# ARM_board.net
KiCad netlist of a schematic drawn in EAGLE
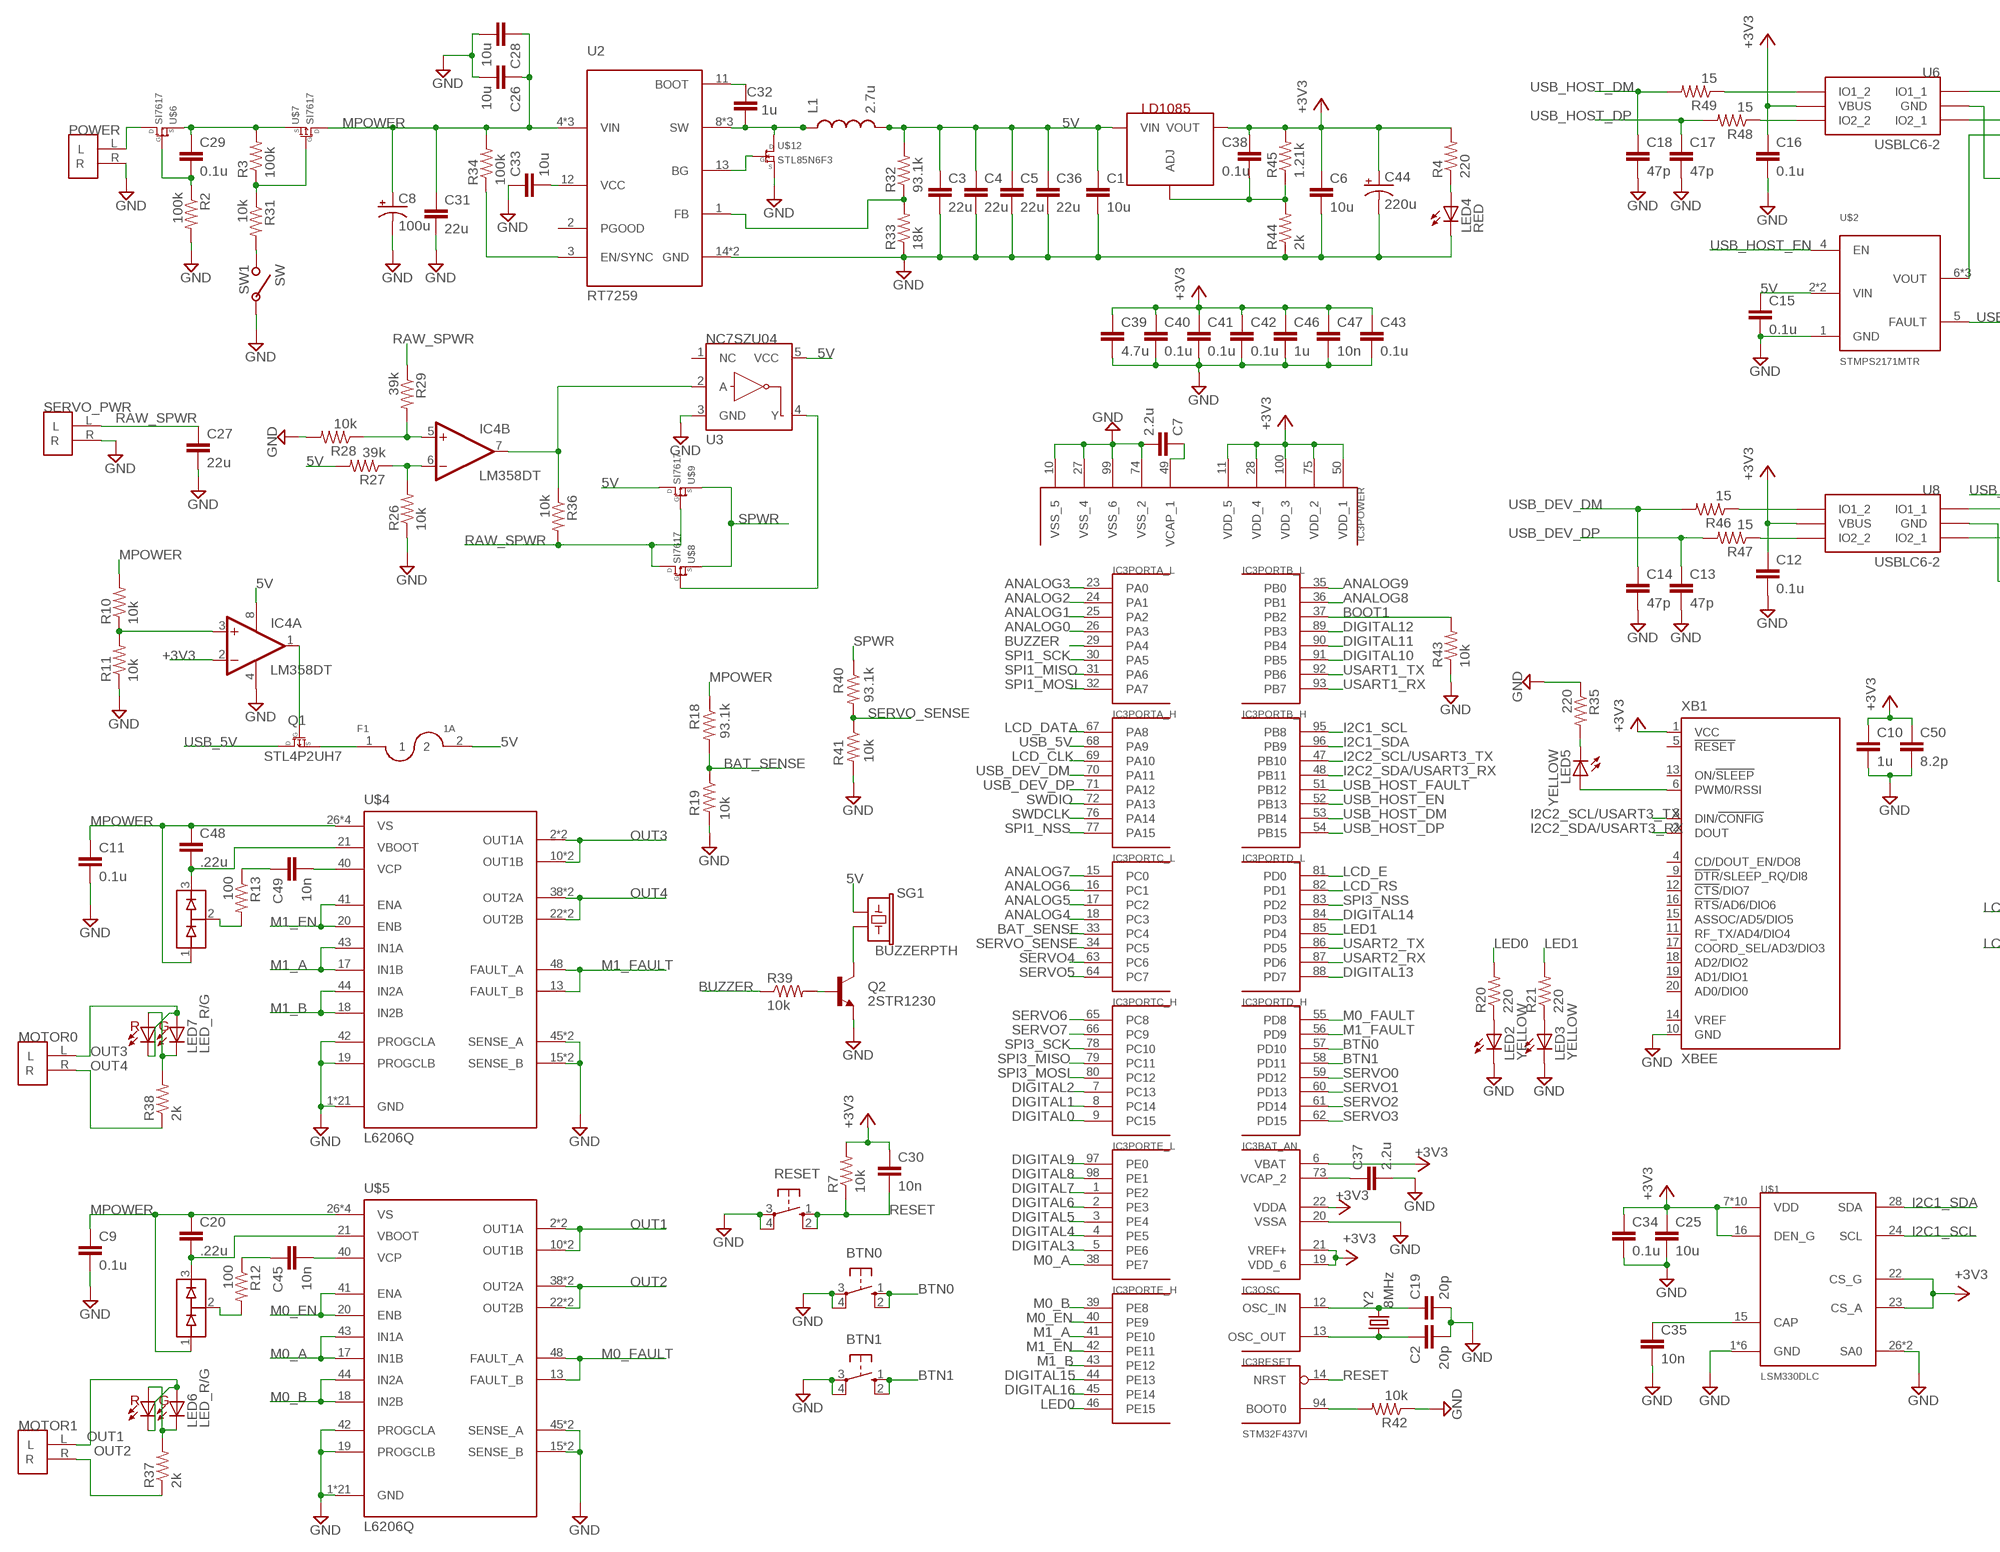
[diagram p0: schematic, sheet 1, part 1 of 2]
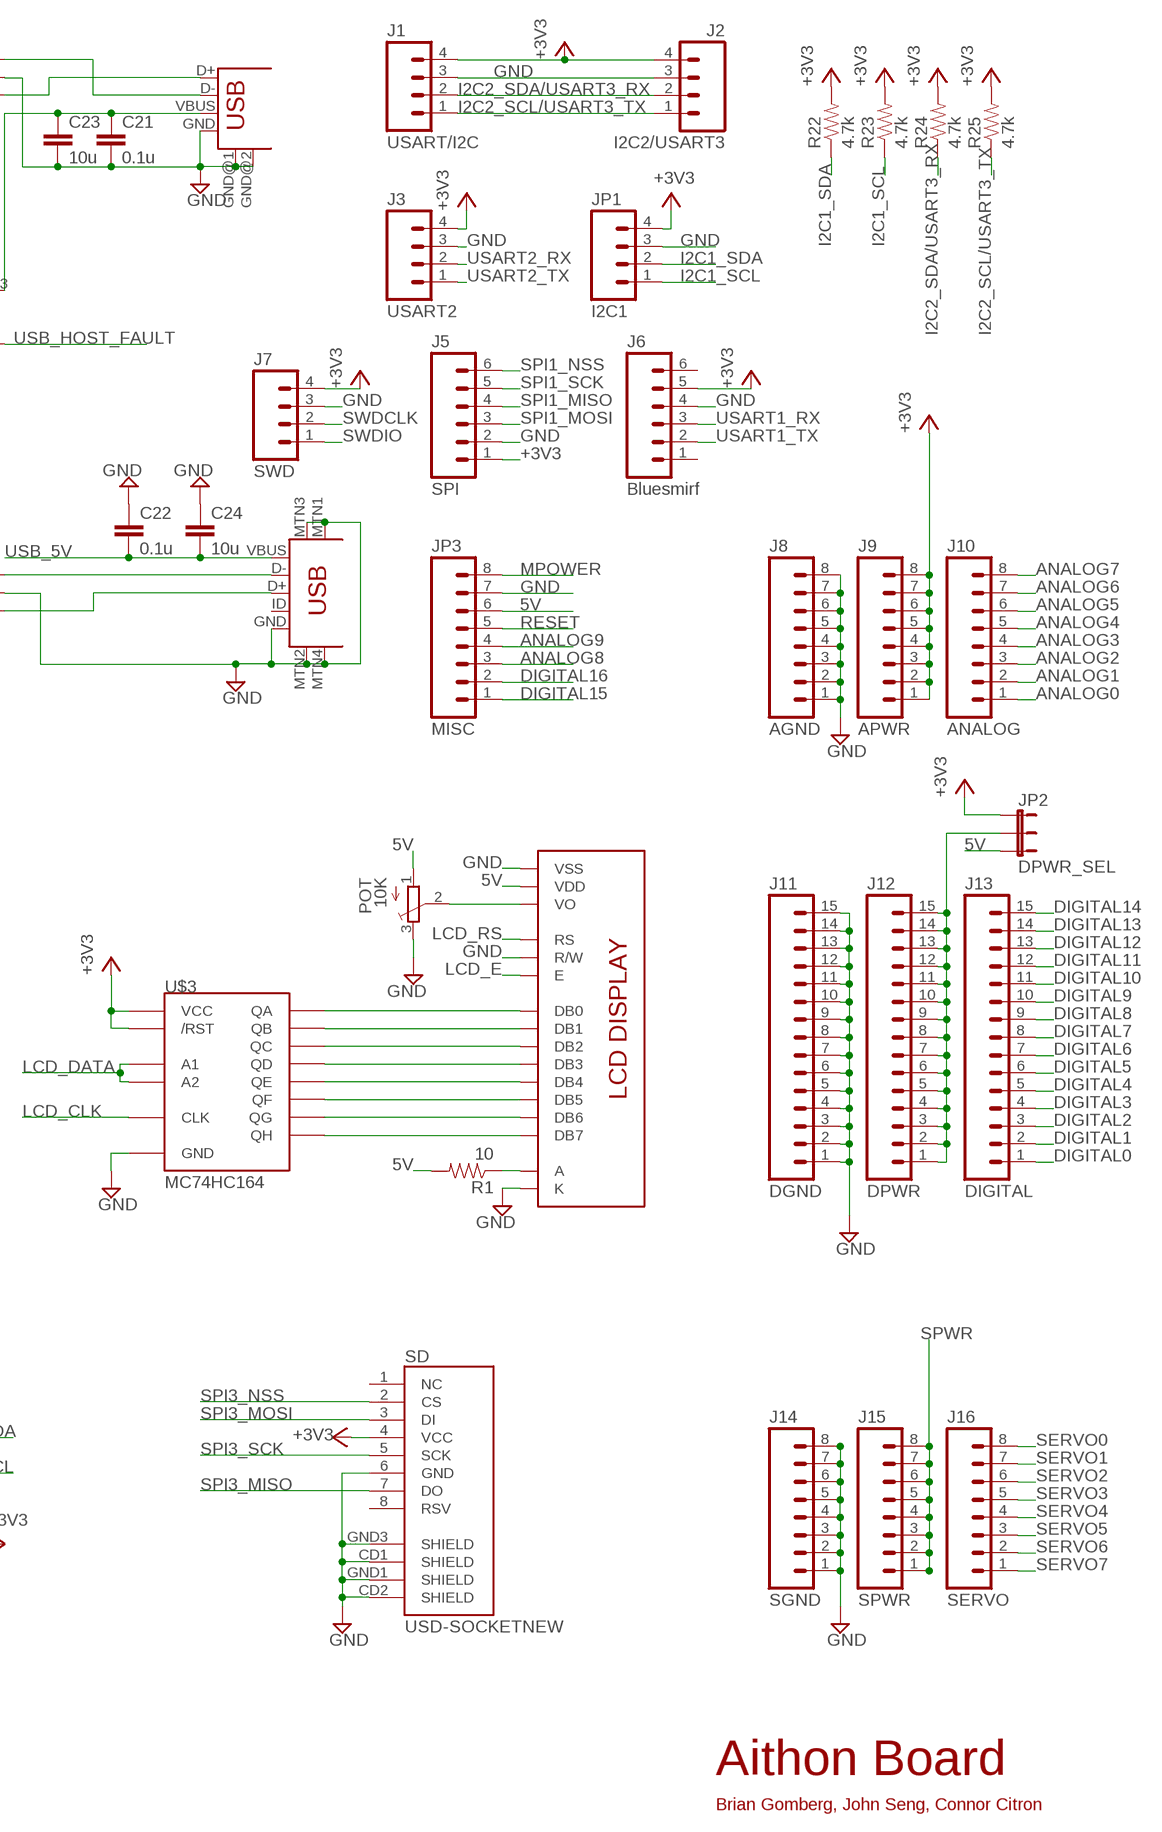
[diagram p1: schematic, sheet 1, part 2 of 2]

(export (version "E")
  (design (tool "Eeschema 10.0.6"))
  (components
    (comp (ref "BTN0")
      (value "10-XX")
      (footprint "eagle-import:B3F-10XX")
      (fields (field (name "MPN") "B3F-1000"))
      (libsource (lib "eagle-import") (part "10-XX"))
    )
    (comp (ref "BTN1")
      (value "10-XX")
      (footprint "eagle-import:B3F-10XX")
      (fields (field (name "MPN") "B3F-1000"))
      (libsource (lib "eagle-import") (part "10-XX"))
    )
    (comp (ref "C1")
      (value "10u")
      (footprint "eagle-import:0603-CAP")
      (libsource (lib "eagle-import") (part "CAP0603-CAP"))
    )
    (comp (ref "C2")
      (value "20p")
      (footprint "eagle-import:0402-CAP")
      (libsource (lib "eagle-import") (part "CAP0402-CAP"))
    )
    (comp (ref "C3")
      (value "22u")
      (footprint "eagle-import:0805")
      (libsource (lib "eagle-import") (part "CAP0805"))
    )
    (comp (ref "C4")
      (value "22u")
      (footprint "eagle-import:0805")
      (libsource (lib "eagle-import") (part "CAP0805"))
    )
    (comp (ref "C5")
      (value "22u")
      (footprint "eagle-import:0805")
      (libsource (lib "eagle-import") (part "CAP0805"))
    )
    (comp (ref "C6")
      (value "10u")
      (footprint "eagle-import:0603-CAP")
      (libsource (lib "eagle-import") (part "CAP0603-CAP"))
    )
    (comp (ref "C7")
      (value "2.2u")
      (footprint "eagle-import:0402-CAP")
      (libsource (lib "eagle-import") (part "CAP0402-CAP"))
    )
    (comp (ref "C8")
      (value "100u")
      (footprint "eagle-import:PANASONIC_D")
      (libsource (lib "eagle-import") (part "CAP_POLD"))
    )
    (comp (ref "C9")
      (value "0.1u")
      (footprint "eagle-import:0603-CAP")
      (libsource (lib "eagle-import") (part "CAP0603-CAP"))
    )
    (comp (ref "C10")
      (value "1u")
      (footprint "eagle-import:0603-CAP")
      (libsource (lib "eagle-import") (part "CAP0603-CAP"))
    )
    (comp (ref "C11")
      (value "0.1u")
      (footprint "eagle-import:0805")
      (libsource (lib "eagle-import") (part "CAP0805"))
    )
    (comp (ref "C12")
      (value "0.1u")
      (footprint "eagle-import:0402-CAP")
      (libsource (lib "eagle-import") (part "CAP0402-CAP"))
    )
    (comp (ref "C13")
      (value "47p")
      (footprint "eagle-import:0402-CAP")
      (libsource (lib "eagle-import") (part "CAP0402-CAP"))
    )
    (comp (ref "C14")
      (value "47p")
      (footprint "eagle-import:0402-CAP")
      (libsource (lib "eagle-import") (part "CAP0402-CAP"))
    )
    (comp (ref "C15")
      (value "0.1u")
      (footprint "eagle-import:0402-CAP")
      (libsource (lib "eagle-import") (part "CAP0402-CAP"))
    )
    (comp (ref "C16")
      (value "0.1u")
      (footprint "eagle-import:0402-CAP")
      (libsource (lib "eagle-import") (part "CAP0402-CAP"))
    )
    (comp (ref "C17")
      (value "47p")
      (footprint "eagle-import:0402-CAP")
      (libsource (lib "eagle-import") (part "CAP0402-CAP"))
    )
    (comp (ref "C18")
      (value "47p")
      (footprint "eagle-import:0402-CAP")
      (libsource (lib "eagle-import") (part "CAP0402-CAP"))
    )
    (comp (ref "C19")
      (value "20p")
      (footprint "eagle-import:0402-CAP")
      (libsource (lib "eagle-import") (part "CAP0402-CAP"))
    )
    (comp (ref "C20")
      (value ".22u")
      (footprint "eagle-import:0402-CAP")
      (libsource (lib "eagle-import") (part "CAP0402-CAP"))
    )
    (comp (ref "C21")
      (value "0.1u")
      (footprint "eagle-import:0402-CAP")
      (libsource (lib "eagle-import") (part "CAP0402-CAP"))
    )
    (comp (ref "C22")
      (value "0.1u")
      (footprint "eagle-import:0402-CAP")
      (libsource (lib "eagle-import") (part "CAP0402-CAP"))
    )
    (comp (ref "C23")
      (value "10u")
      (footprint "eagle-import:0805")
      (libsource (lib "eagle-import") (part "CAP0805"))
    )
    (comp (ref "C24")
      (value "10u")
      (footprint "eagle-import:0805")
      (libsource (lib "eagle-import") (part "CAP0805"))
    )
    (comp (ref "C25")
      (value "10u")
      (footprint "eagle-import:0603-CAP")
      (libsource (lib "eagle-import") (part "CAP0603-CAP"))
    )
    (comp (ref "C26")
      (value "10u")
      (footprint "eagle-import:0805")
      (libsource (lib "eagle-import") (part "CAP0805"))
    )
    (comp (ref "C27")
      (value "22u")
      (footprint "eagle-import:1206")
      (libsource (lib "eagle-import") (part "CAP1206"))
    )
    (comp (ref "C28")
      (value "10u")
      (footprint "eagle-import:0805")
      (libsource (lib "eagle-import") (part "CAP0805"))
    )
    (comp (ref "C29")
      (value "0.1u")
      (footprint "eagle-import:0402-CAP")
      (libsource (lib "eagle-import") (part "CAP0402-CAP"))
    )
    (comp (ref "C30")
      (value "10n")
      (footprint "eagle-import:0402-CAP")
      (libsource (lib "eagle-import") (part "CAP0402-CAP"))
    )
    (comp (ref "C31")
      (value "22u")
      (footprint "eagle-import:1206")
      (libsource (lib "eagle-import") (part "CAP1206"))
    )
    (comp (ref "C32")
      (value "1u")
      (footprint "eagle-import:0603-CAP")
      (libsource (lib "eagle-import") (part "CAP0603-CAP"))
    )
    (comp (ref "C33")
      (value "10u")
      (footprint "eagle-import:0603-CAP")
      (libsource (lib "eagle-import") (part "CAP0603-CAP"))
    )
    (comp (ref "C34")
      (value "0.1u")
      (footprint "eagle-import:0402-CAP")
      (libsource (lib "eagle-import") (part "CAP0402-CAP"))
    )
    (comp (ref "C35")
      (value "10n")
      (footprint "eagle-import:0402-CAP")
      (libsource (lib "eagle-import") (part "CAP0402-CAP"))
    )
    (comp (ref "C36")
      (value "22u")
      (footprint "eagle-import:0805")
      (libsource (lib "eagle-import") (part "CAP0805"))
    )
    (comp (ref "C37")
      (value "2.2u")
      (footprint "eagle-import:0402-CAP")
      (libsource (lib "eagle-import") (part "CAP0402-CAP"))
    )
    (comp (ref "C38")
      (value "0.1u")
      (footprint "eagle-import:0402-CAP")
      (libsource (lib "eagle-import") (part "CAP0402-CAP"))
    )
    (comp (ref "C39")
      (value "4.7u")
      (footprint "eagle-import:0603-CAP")
      (libsource (lib "eagle-import") (part "CAP0603-CAP"))
    )
    (comp (ref "C40")
      (value "0.1u")
      (footprint "eagle-import:0402-CAP")
      (libsource (lib "eagle-import") (part "CAP0402-CAP"))
    )
    (comp (ref "C41")
      (value "0.1u")
      (footprint "eagle-import:0402-CAP")
      (libsource (lib "eagle-import") (part "CAP0402-CAP"))
    )
    (comp (ref "C42")
      (value "0.1u")
      (footprint "eagle-import:0402-CAP")
      (libsource (lib "eagle-import") (part "CAP0402-CAP"))
    )
    (comp (ref "C43")
      (value "0.1u")
      (footprint "eagle-import:0402-CAP")
      (libsource (lib "eagle-import") (part "CAP0402-CAP"))
    )
    (comp (ref "C44")
      (value "220u")
      (footprint "eagle-import:PANASONIC_D")
      (libsource (lib "eagle-import") (part "CAP_POLD"))
    )
    (comp (ref "C45")
      (value "10n")
      (footprint "eagle-import:0402-CAP")
      (libsource (lib "eagle-import") (part "CAP0402-CAP"))
    )
    (comp (ref "C46")
      (value "1u")
      (footprint "eagle-import:0402-CAP")
      (libsource (lib "eagle-import") (part "CAP0402-CAP"))
    )
    (comp (ref "C47")
      (value "10n")
      (footprint "eagle-import:0402-CAP")
      (libsource (lib "eagle-import") (part "CAP0402-CAP"))
    )
    (comp (ref "C48")
      (value ".22u")
      (footprint "eagle-import:0402-CAP")
      (libsource (lib "eagle-import") (part "CAP0402-CAP"))
    )
    (comp (ref "C49")
      (value "10n")
      (footprint "eagle-import:0402-CAP")
      (libsource (lib "eagle-import") (part "CAP0402-CAP"))
    )
    (comp (ref "C50")
      (value "8.2p")
      (footprint "eagle-import:0402-CAP")
      (libsource (lib "eagle-import") (part "CAP0402-CAP"))
    )
    (comp (ref "F1")
      (value "1A")
      (footprint "eagle-import:1206")
      (libsource (lib "eagle-import") (part "POLYFUSE"))
    )
    (comp (ref "IC3")
      (value "STM32F437VI")
      (footprint "eagle-import:TQFP100")
      (libsource (lib "eagle-import") (part "STM32F407VET"))
    )
    (comp (ref "IC4")
      (value "LM358DT")
      (footprint "eagle-import:SO08")
      (libsource (lib "eagle-import") (part "LM358D"))
    )
    (comp (ref "J1")
      (value "USART/I2C")
      (footprint "eagle-import:1X04")
      (libsource (lib "eagle-import") (part "M04PTH"))
    )
    (comp (ref "J2")
      (value "I2C2/USART3")
      (footprint "eagle-import:1X04")
      (libsource (lib "eagle-import") (part "M04PTH"))
    )
    (comp (ref "J3")
      (value "USART2")
      (footprint "eagle-import:1X04")
      (libsource (lib "eagle-import") (part "M04PTH"))
    )
    (comp (ref "J5")
      (value "SPI")
      (footprint "eagle-import:1X06")
      (libsource (lib "eagle-import") (part "M06SIP"))
    )
    (comp (ref "J6")
      (value "Bluesmirf")
      (footprint "eagle-import:1X06")
      (libsource (lib "eagle-import") (part "M06SIP"))
    )
    (comp (ref "J7")
      (value "SWD")
      (footprint "eagle-import:1X04")
      (libsource (lib "eagle-import") (part "M04PTH"))
    )
    (comp (ref "J8")
      (value "AGND")
      (footprint "eagle-import:1X08")
      (libsource (lib "eagle-import") (part "M081X08"))
    )
    (comp (ref "J9")
      (value "APWR")
      (footprint "eagle-import:1X08")
      (libsource (lib "eagle-import") (part "M081X08"))
    )
    (comp (ref "J10")
      (value "ANALOG")
      (footprint "eagle-import:1X08")
      (libsource (lib "eagle-import") (part "M081X08"))
    )
    (comp (ref "J11")
      (value "DGND")
      (footprint "eagle-import:1X15")
      (libsource (lib "eagle-import") (part "M15"))
    )
    (comp (ref "J12")
      (value "DPWR")
      (footprint "eagle-import:1X15")
      (libsource (lib "eagle-import") (part "M15"))
    )
    (comp (ref "J13")
      (value "DIGITAL")
      (footprint "eagle-import:1X15")
      (libsource (lib "eagle-import") (part "M15"))
    )
    (comp (ref "J14")
      (value "SGND")
      (footprint "eagle-import:1X08")
      (libsource (lib "eagle-import") (part "M081X08"))
    )
    (comp (ref "J15")
      (value "SPWR")
      (footprint "eagle-import:1X08")
      (libsource (lib "eagle-import") (part "M081X08"))
    )
    (comp (ref "J16")
      (value "SERVO")
      (footprint "eagle-import:1X08")
      (libsource (lib "eagle-import") (part "M081X08"))
    )
    (comp (ref "JP1")
      (value "I2C1")
      (footprint "eagle-import:1X04")
      (libsource (lib "eagle-import") (part "M04PTH"))
    )
    (comp (ref "JP2")
      (value "DPWR_SEL")
      (footprint "eagle-import:1X03")
      (libsource (lib "eagle-import") (part "JUMPER-3PTH"))
    )
    (comp (ref "JP3")
      (value "MISC")
      (footprint "eagle-import:1X08")
      (libsource (lib "eagle-import") (part "M081X08"))
    )
    (comp (ref "L1")
      (value "2.7u")
      (footprint "eagle-import:INDUCTOR")
      (libsource (lib "eagle-import") (part "INDUCTOR"))
    )
    (comp (ref "LCD")
      (value "LCD_DISPLAY")
      (footprint "eagle-import:LCD")
      (libsource (lib "eagle-import") (part "LCD_DISPLAY"))
    )
    (comp (ref "LD1085")
      (value "AP1084")
      (footprint "eagle-import:DPAK")
      (libsource (lib "eagle-import") (part "AP1084"))
    )
    (comp (ref "LED2")
      (value "YELLOW")
      (footprint "eagle-import:CHIP-LED0603")
      (libsource (lib "eagle-import") (part "LEDCHIP-LED0603"))
    )
    (comp (ref "LED3")
      (value "YELLOW")
      (footprint "eagle-import:CHIP-LED0603")
      (libsource (lib "eagle-import") (part "LEDCHIP-LED0603"))
    )
    (comp (ref "LED4")
      (value "RED")
      (footprint "eagle-import:CHIP-LED0603")
      (libsource (lib "eagle-import") (part "LEDCHIP-LED0603"))
    )
    (comp (ref "LED5")
      (value "YELLOW")
      (footprint "eagle-import:CHIP-LED0603")
      (libsource (lib "eagle-import") (part "LEDCHIP-LED0603"))
    )
    (comp (ref "LED6")
      (value "LED_R/G")
      (footprint "eagle-import:LED-0606")
      (libsource (lib "eagle-import") (part "LED_BICOLOR"))
    )
    (comp (ref "LED7")
      (value "LED_R/G")
      (footprint "eagle-import:LED-0606")
      (libsource (lib "eagle-import") (part "LED_BICOLOR"))
    )
    (comp (ref "MOTOR0")
      (value "2POS_TERMINAL")
      (footprint "eagle-import:2POS_TERMINAL")
      (libsource (lib "eagle-import") (part "2POS_TERMINAL"))
    )
    (comp (ref "MOTOR1")
      (value "2POS_TERMINAL")
      (footprint "eagle-import:2POS_TERMINAL")
      (libsource (lib "eagle-import") (part "2POS_TERMINAL"))
    )
    (comp (ref "POT")
      (value "10K")
      (footprint "eagle-import:POT")
      (libsource (lib "eagle-import") (part "POT"))
    )
    (comp (ref "POWER")
      (value "2POS_TERMINAL")
      (footprint "eagle-import:2POS_TERMINAL")
      (libsource (lib "eagle-import") (part "2POS_TERMINAL"))
    )
    (comp (ref "Q1")
      (value "STL4P2UH7")
      (footprint "eagle-import:POWERFLAT")
      (libsource (lib "eagle-import") (part "STL4P2UH7"))
    )
    (comp (ref "Q2")
      (value "2STR1230")
      (footprint "eagle-import:SOT23-3")
      (libsource (lib "eagle-import") (part "TRANSISTOR_NPNSOT23-3"))
    )
    (comp (ref "R1")
      (value "10")
      (footprint "eagle-import:0402-RES")
      (libsource (lib "eagle-import") (part "RESISTOR0402-RES"))
    )
    (comp (ref "R2")
      (value "100k")
      (footprint "eagle-import:0402-RES")
      (libsource (lib "eagle-import") (part "RESISTOR0402-RES"))
    )
    (comp (ref "R3")
      (value "100k")
      (footprint "eagle-import:0402-RES")
      (libsource (lib "eagle-import") (part "RESISTOR0402-RES"))
    )
    (comp (ref "R4")
      (value "220")
      (footprint "eagle-import:0402-RES")
      (libsource (lib "eagle-import") (part "RESISTOR0402-RES"))
    )
    (comp (ref "R7")
      (value "10k")
      (footprint "eagle-import:0402-RES")
      (libsource (lib "eagle-import") (part "RESISTOR0402-RES"))
    )
    (comp (ref "R10")
      (value "10k")
      (footprint "eagle-import:0402-RES")
      (libsource (lib "eagle-import") (part "RESISTOR0402-RES"))
    )
    (comp (ref "R11")
      (value "10k")
      (footprint "eagle-import:0402-RES")
      (libsource (lib "eagle-import") (part "RESISTOR0402-RES"))
    )
    (comp (ref "R12")
      (value "100")
      (footprint "eagle-import:0402-RES")
      (libsource (lib "eagle-import") (part "RESISTOR0402-RES"))
    )
    (comp (ref "R13")
      (value "100")
      (footprint "eagle-import:0402-RES")
      (libsource (lib "eagle-import") (part "RESISTOR0402-RES"))
    )
    (comp (ref "R18")
      (value "93.1k")
      (footprint "eagle-import:0402-RES")
      (libsource (lib "eagle-import") (part "RESISTOR0402-RES"))
    )
    (comp (ref "R19")
      (value "10k")
      (footprint "eagle-import:0402-RES")
      (libsource (lib "eagle-import") (part "RESISTOR0402-RES"))
    )
    (comp (ref "R20")
      (value "220")
      (footprint "eagle-import:0402-RES")
      (libsource (lib "eagle-import") (part "RESISTOR0402-RES"))
    )
    (comp (ref "R21")
      (value "220")
      (footprint "eagle-import:0402-RES")
      (libsource (lib "eagle-import") (part "RESISTOR0402-RES"))
    )
    (comp (ref "R22")
      (value "4.7k")
      (footprint "eagle-import:0402-RES")
      (libsource (lib "eagle-import") (part "RESISTOR0402-RES"))
    )
    (comp (ref "R23")
      (value "4.7k")
      (footprint "eagle-import:0402-RES")
      (libsource (lib "eagle-import") (part "RESISTOR0402-RES"))
    )
    (comp (ref "R24")
      (value "4.7k")
      (footprint "eagle-import:0402-RES")
      (libsource (lib "eagle-import") (part "RESISTOR0402-RES"))
    )
    (comp (ref "R25")
      (value "4.7k")
      (footprint "eagle-import:0402-RES")
      (libsource (lib "eagle-import") (part "RESISTOR0402-RES"))
    )
    (comp (ref "R26")
      (value "10k")
      (footprint "eagle-import:0402-RES")
      (libsource (lib "eagle-import") (part "RESISTOR0402-RES"))
    )
    (comp (ref "R27")
      (value "39k")
      (footprint "eagle-import:0402-RES")
      (libsource (lib "eagle-import") (part "RESISTOR0402-RES"))
    )
    (comp (ref "R28")
      (value "10k")
      (footprint "eagle-import:0402-RES")
      (libsource (lib "eagle-import") (part "RESISTOR0402-RES"))
    )
    (comp (ref "R29")
      (value "39k")
      (footprint "eagle-import:0402-RES")
      (libsource (lib "eagle-import") (part "RESISTOR0402-RES"))
    )
    (comp (ref "R31")
      (value "10k")
      (footprint "eagle-import:0402-RES")
      (libsource (lib "eagle-import") (part "RESISTOR0402-RES"))
    )
    (comp (ref "R32")
      (value "93.1k")
      (footprint "eagle-import:0402-RES")
      (libsource (lib "eagle-import") (part "RESISTOR0402-RES"))
    )
    (comp (ref "R33")
      (value "18k")
      (footprint "eagle-import:0402-RES")
      (libsource (lib "eagle-import") (part "RESISTOR0402-RES"))
    )
    (comp (ref "R34")
      (value "100k")
      (footprint "eagle-import:0402-RES")
      (libsource (lib "eagle-import") (part "RESISTOR0402-RES"))
    )
    (comp (ref "R35")
      (value "220")
      (footprint "eagle-import:0402-RES")
      (libsource (lib "eagle-import") (part "RESISTOR0402-RES"))
    )
    (comp (ref "R36")
      (value "10k")
      (footprint "eagle-import:0402-RES")
      (libsource (lib "eagle-import") (part "RESISTOR0402-RES"))
    )
    (comp (ref "R37")
      (value "2k")
      (footprint "eagle-import:0402-RES")
      (libsource (lib "eagle-import") (part "RESISTOR0402-RES"))
    )
    (comp (ref "R38")
      (value "2k")
      (footprint "eagle-import:0402-RES")
      (libsource (lib "eagle-import") (part "RESISTOR0402-RES"))
    )
    (comp (ref "R39")
      (value "10k")
      (footprint "eagle-import:0402-RES")
      (libsource (lib "eagle-import") (part "RESISTOR0402-RES"))
    )
    (comp (ref "R40")
      (value "93.1k")
      (footprint "eagle-import:0402-RES")
      (libsource (lib "eagle-import") (part "RESISTOR0402-RES"))
    )
    (comp (ref "R41")
      (value "10k")
      (footprint "eagle-import:0402-RES")
      (libsource (lib "eagle-import") (part "RESISTOR0402-RES"))
    )
    (comp (ref "R42")
      (value "10k")
      (footprint "eagle-import:0402-RES")
      (libsource (lib "eagle-import") (part "RESISTOR0402-RES"))
    )
    (comp (ref "R43")
      (value "10k")
      (footprint "eagle-import:0402-RES")
      (libsource (lib "eagle-import") (part "RESISTOR0402-RES"))
    )
    (comp (ref "R44")
      (value "2k")
      (footprint "eagle-import:0402-RES")
      (libsource (lib "eagle-import") (part "RESISTOR0402-RES"))
    )
    (comp (ref "R45")
      (value "1.21k")
      (footprint "eagle-import:0402-RES")
      (libsource (lib "eagle-import") (part "RESISTOR0402-RES"))
    )
    (comp (ref "R46")
      (value "15")
      (footprint "eagle-import:0402-RES")
      (libsource (lib "eagle-import") (part "RESISTOR0402-RES"))
    )
    (comp (ref "R47")
      (value "15")
      (footprint "eagle-import:0402-RES")
      (libsource (lib "eagle-import") (part "RESISTOR0402-RES"))
    )
    (comp (ref "R48")
      (value "15")
      (footprint "eagle-import:0402-RES")
      (libsource (lib "eagle-import") (part "RESISTOR0402-RES"))
    )
    (comp (ref "R49")
      (value "15")
      (footprint "eagle-import:0402-RES")
      (libsource (lib "eagle-import") (part "RESISTOR0402-RES"))
    )
    (comp (ref "RESET")
      (value "10-XX")
      (footprint "eagle-import:B3F-10XX")
      (fields (field (name "MPN") "B3F-1000"))
      (libsource (lib "eagle-import") (part "10-XX"))
    )
    (comp (ref "SD")
      (value "USD-SOCKETNEW")
      (footprint "eagle-import:MICRO-SD-SOCKET-PP")
      (libsource (lib "eagle-import") (part "USD-SOCKETNEW"))
    )
    (comp (ref "SERVO_PWR")
      (value "2POS_TERMINAL")
      (footprint "eagle-import:2POS_TERMINAL")
      (libsource (lib "eagle-import") (part "2POS_TERMINAL"))
    )
    (comp (ref "SG1")
      (value "BUZZERPTH")
      (footprint "eagle-import:BUZZER-12MM")
      (libsource (lib "eagle-import") (part "BUZZERPTH"))
    )
    (comp (ref "SW1") (value "SW") (footprint "eagle-import:SW") (libsource (lib "eagle-import") (part "SW")))
    (comp (ref "U$1")
      (value "LSM330DLC")
      (footprint "eagle-import:LGA-28")
      (libsource (lib "eagle-import") (part "LSM330DLC"))
    )
    (comp (ref "U$2")
      (value "STMPS2171MTR")
      (footprint "eagle-import:8-SOIC")
      (libsource (lib "eagle-import") (part "RT9715"))
    )
    (comp (ref "U$3")
      (value "MC74HC164")
      (footprint "eagle-import:TSSOP-14")
      (libsource (lib "eagle-import") (part "MC74HC164"))
    )
    (comp (ref "U$4")
      (value "L6206Q")
      (footprint "eagle-import:VFQFPN48")
      (libsource (lib "eagle-import") (part "L6206Q"))
    )
    (comp (ref "U$5")
      (value "L6206Q")
      (footprint "eagle-import:VFQFPN48")
      (libsource (lib "eagle-import") (part "L6206Q"))
    )
    (comp (ref "U$6")
      (value "SI7617")
      (footprint "eagle-import:POWERPAK1212-8")
      (libsource (lib "eagle-import") (part "SI7617"))
    )
    (comp (ref "U$7")
      (value "SI7617")
      (footprint "eagle-import:POWERPAK1212-8")
      (libsource (lib "eagle-import") (part "SI7617"))
    )
    (comp (ref "U$8")
      (value "SI7617")
      (footprint "eagle-import:POWERPAK1212-8")
      (libsource (lib "eagle-import") (part "SI7617"))
    )
    (comp (ref "U$9")
      (value "SI7617")
      (footprint "eagle-import:POWERPAK1212-8")
      (libsource (lib "eagle-import") (part "SI7617"))
    )
    (comp (ref "U$10")
      (value "BAV99")
      (footprint "eagle-import:SOT-23")
      (libsource (lib "eagle-import") (part "BAV99"))
    )
    (comp (ref "U$11")
      (value "BAV99")
      (footprint "eagle-import:SOT-23")
      (libsource (lib "eagle-import") (part "BAV99"))
    )
    (comp (ref "U$12")
      (value "STL85N6F3")
      (footprint "eagle-import:POWERFLAT5X6")
      (libsource (lib "eagle-import") (part "STL85N6F3"))
    )
    (comp (ref "U2")
      (value "RT7259")
      (footprint "eagle-import:WDFN-14L")
      (libsource (lib "eagle-import") (part "SWITCHING_REG"))
    )
    (comp (ref "U3")
      (value "NC7SZU04")
      (footprint "eagle-import:SC70")
      (libsource (lib "eagle-import") (part "INVERTER{dblquote}{dblquote}"))
    )
    (comp (ref "U6")
      (value "USBLC6-2")
      (footprint "eagle-import:SOT23-6L")
      (libsource (lib "eagle-import") (part "USBLC6-2"))
    )
    (comp (ref "U8")
      (value "USBLC6-2")
      (footprint "eagle-import:SOT23-6L")
      (libsource (lib "eagle-import") (part "USBLC6-2"))
    )
    (comp (ref "USB1")
      (value "USB-A-S")
      (footprint "eagle-import:USB-A-S")
      (libsource (lib "eagle-import") (part "USB-A-S"))
    )
    (comp (ref "USB2")
      (value "USB-MINIB-5PIN")
      (footprint "eagle-import:USB-MINIB")
      (libsource (lib "eagle-import") (part "USB-MINIB-5PIN"))
    )
    (comp (ref "XB1")
      (value "XBEE")
      (footprint "eagle-import:XBEE")
      (fields
        (field (name "MPN") "XBP24-Z7UIT-004")
        (field (name "MPN_1") "XBP24-Z7UIT-004")
        (field (name "OC_FARNELL") "1751799")
        (field (name "OC_NEWARK") "34R5507")
      )
      (libsource (lib "eagle-import") (part "XBEE"))
    )
    (comp (ref "Y2")
      (value "8MHz")
      (footprint "eagle-import:HC49UP")
      (libsource (lib "eagle-import") (part "CRYSTALSMD"))
    )
  )
  (nets
    (net (code "1") (name "+3V3") (class "Default")
      (node (ref "C10") (pin "1") (pinfunction "1_1") (pintype "passive"))
      (node (ref "C12") (pin "1") (pinfunction "1_1") (pintype "passive"))
      (node (ref "C16") (pin "1") (pinfunction "1_1") (pintype "passive"))
      (node (ref "C25") (pin "1") (pinfunction "1_1") (pintype "passive"))
      (node (ref "C30") (pin "1") (pinfunction "1_1") (pintype "passive"))
      (node (ref "C34") (pin "1") (pinfunction "1_1") (pintype "passive"))
      (node (ref "C38") (pin "1") (pinfunction "1_1") (pintype "passive"))
      (node (ref "C39") (pin "1") (pinfunction "1_1") (pintype "passive"))
      (node (ref "C40") (pin "1") (pinfunction "1_1") (pintype "passive"))
      (node (ref "C41") (pin "1") (pinfunction "1_1") (pintype "passive"))
      (node (ref "C42") (pin "1") (pinfunction "1_1") (pintype "passive"))
      (node (ref "C43") (pin "1") (pinfunction "1_1") (pintype "passive"))
      (node (ref "C44") (pin "+") (pinfunction "+_+") (pintype "passive"))
      (node (ref "C46") (pin "1") (pinfunction "1_1") (pintype "passive"))
      (node (ref "C47") (pin "1") (pinfunction "1_1") (pintype "passive"))
      (node (ref "C50") (pin "1") (pinfunction "1_1") (pintype "passive"))
      (node (ref "C6") (pin "1") (pinfunction "1_1") (pintype "passive"))
      (node (ref "IC3") (pin "100") (pinfunction "VDD_3_100") (pintype "power_in"))
      (node (ref "IC3") (pin "11") (pinfunction "VDD_5_11") (pintype "power_in"))
      (node (ref "IC3") (pin "19") (pinfunction "VDD_6_19") (pintype "input"))
      (node (ref "IC3") (pin "21") (pinfunction "VREF+_21") (pintype "input"))
      (node (ref "IC3") (pin "22") (pinfunction "VDDA_22") (pintype "power_in"))
      (node (ref "IC3") (pin "28") (pinfunction "VDD_4_28") (pintype "power_in"))
      (node (ref "IC3") (pin "50") (pinfunction "VDD_1_50") (pintype "power_in"))
      (node (ref "IC3") (pin "6") (pinfunction "VBAT_6") (pintype "power_in"))
      (node (ref "IC3") (pin "75") (pinfunction "VDD_2_75") (pintype "power_in"))
      (node (ref "IC4") (pin "2") (pinfunction "-IN_2") (pintype "input"))
      (node (ref "J1") (pin "4") (pinfunction "4_4") (pintype "passive"))
      (node (ref "J2") (pin "4") (pinfunction "4_4") (pintype "passive"))
      (node (ref "J3") (pin "4") (pinfunction "4_4") (pintype "passive"))
      (node (ref "J5") (pin "1") (pinfunction "1_1") (pintype "passive"))
      (node (ref "J6") (pin "5") (pinfunction "5_5") (pintype "passive"))
      (node (ref "J7") (pin "4") (pinfunction "4_4") (pintype "passive"))
      (node (ref "J9") (pin "1") (pinfunction "1_1") (pintype "passive"))
      (node (ref "J9") (pin "2") (pinfunction "2_2") (pintype "passive"))
      (node (ref "J9") (pin "3") (pinfunction "3_3") (pintype "passive"))
      (node (ref "J9") (pin "4") (pinfunction "4_4") (pintype "passive"))
      (node (ref "J9") (pin "5") (pinfunction "5_5") (pintype "passive"))
      (node (ref "J9") (pin "6") (pinfunction "6_6") (pintype "passive"))
      (node (ref "J9") (pin "7") (pinfunction "7_7") (pintype "passive"))
      (node (ref "J9") (pin "8") (pinfunction "8_8") (pintype "passive"))
      (node (ref "JP1") (pin "4") (pinfunction "4_4") (pintype "passive"))
      (node (ref "JP2") (pin "1") (pinfunction "1_1") (pintype "passive"))
      (node (ref "LD1085") (pin "TAB") (pinfunction "VOUT_TAB") (pintype "bidirectional"))
      (node (ref "R22") (pin "2") (pinfunction "2_2") (pintype "passive"))
      (node (ref "R23") (pin "2") (pinfunction "2_2") (pintype "passive"))
      (node (ref "R24") (pin "2") (pinfunction "2_2") (pintype "passive"))
      (node (ref "R25") (pin "2") (pinfunction "2_2") (pintype "passive"))
      (node (ref "R4") (pin "2") (pinfunction "2_2") (pintype "passive"))
      (node (ref "R45") (pin "2") (pinfunction "2_2") (pintype "passive"))
      (node (ref "R7") (pin "2") (pinfunction "2_2") (pintype "passive"))
      (node (ref "SD") (pin "4") (pinfunction "VCC_4") (pintype "bidirectional"))
      (node (ref "U$1") (pin "10") (pinfunction "VDD_10") (pintype "bidirectional"))
      (node (ref "U$1") (pin "11") (pinfunction "VDD_11") (pintype "bidirectional"))
      (node (ref "U$1") (pin "12") (pinfunction "VDD_12") (pintype "bidirectional"))
      (node (ref "U$1") (pin "13") (pinfunction "VDD_13") (pintype "bidirectional"))
      (node (ref "U$1") (pin "14") (pinfunction "VDD_14") (pintype "bidirectional"))
      (node (ref "U$1") (pin "16") (pinfunction "DEN_G_16") (pintype "bidirectional"))
      (node (ref "U$1") (pin "21") (pinfunction "VDD_21") (pintype "bidirectional"))
      (node (ref "U$1") (pin "22") (pinfunction "CS_G_22") (pintype "bidirectional"))
      (node (ref "U$1") (pin "23") (pinfunction "CS_A_23") (pintype "bidirectional"))
      (node (ref "U$1") (pin "25") (pinfunction "VDD_25") (pintype "bidirectional"))
      (node (ref "U$1") (pin "7") (pinfunction "VDD_7") (pintype "bidirectional"))
      (node (ref "U$1") (pin "8") (pinfunction "VDD_8") (pintype "bidirectional"))
      (node (ref "U$1") (pin "9") (pinfunction "VDD_9") (pintype "bidirectional"))
      (node (ref "U$3") (pin "14") (pinfunction "VCC_14") (pintype "bidirectional"))
      (node (ref "U$3") (pin "9") (pinfunction "/RST_9") (pintype "bidirectional"))
      (node (ref "U6") (pin "P$5") (pinfunction "VBUS_P$5") (pintype "bidirectional"))
      (node (ref "U8") (pin "P$5") (pinfunction "VBUS_P$5") (pintype "bidirectional"))
      (node (ref "XB1") (pin "1") (pinfunction "VCC_1") (pintype "power_in"))
    )
    (net (code "2") (name "/5V") (class "Default")
      (node (ref "C1") (pin "1") (pinfunction "1_1") (pintype "passive"))
      (node (ref "C15") (pin "1") (pinfunction "1_1") (pintype "passive"))
      (node (ref "C3") (pin "1") (pinfunction "1_1") (pintype "passive"))
      (node (ref "C36") (pin "1") (pinfunction "1_1") (pintype "passive"))
      (node (ref "C4") (pin "1") (pinfunction "1_1") (pintype "passive"))
      (node (ref "C5") (pin "1") (pinfunction "1_1") (pintype "passive"))
      (node (ref "F1") (pin "2") (pinfunction "2_2") (pintype "bidirectional"))
      (node (ref "IC4") (pin "8") (pinfunction "V+_8") (pintype "power_in"))
      (node (ref "JP2") (pin "3") (pinfunction "3_3") (pintype "passive"))
      (node (ref "JP3") (pin "6") (pinfunction "6_6") (pintype "passive"))
      (node (ref "L1") (pin "P$2") (pinfunction "2_P$2") (pintype "passive"))
      (node (ref "LCD") (pin "VDD") (pinfunction "VDD_VDD") (pintype "bidirectional"))
      (node (ref "LD1085") (pin "3") (pinfunction "VIN_3") (pintype "bidirectional"))
      (node (ref "POT") (pin "1") (pinfunction "A_1") (pintype "passive"))
      (node (ref "R1") (pin "2") (pinfunction "2_2") (pintype "passive"))
      (node (ref "R27") (pin "2") (pinfunction "2_2") (pintype "passive"))
      (node (ref "R32") (pin "2") (pinfunction "2_2") (pintype "passive"))
      (node (ref "SG1") (pin "+") (pinfunction "1_+") (pintype "passive"))
      (node (ref "U$2") (pin "2") (pinfunction "VIN_2") (pintype "bidirectional"))
      (node (ref "U$2") (pin "3") (pinfunction "VIN_3") (pintype "bidirectional"))
      (node (ref "U$9") (pin "5") (pinfunction "D_5") (pintype "bidirectional"))
      (node (ref "U$9") (pin "6") (pinfunction "D_6") (pintype "bidirectional"))
      (node (ref "U$9") (pin "7") (pinfunction "D_7") (pintype "bidirectional"))
      (node (ref "U$9") (pin "8") (pinfunction "D_8") (pintype "bidirectional"))
      (node (ref "U$9") (pin "PAD") (pinfunction "D_PAD") (pintype "bidirectional"))
      (node (ref "U3") (pin "5") (pinfunction "VCC_5") (pintype "bidirectional"))
    )
    (net (code "3") (name "/ANALOG0") (class "Default")
      (node (ref "IC3") (pin "26") (pinfunction "PA3_26") (pintype "bidirectional"))
      (node (ref "J10") (pin "1") (pinfunction "1_1") (pintype "passive"))
    )
    (net (code "4") (name "/ANALOG1") (class "Default")
      (node (ref "IC3") (pin "25") (pinfunction "PA2_25") (pintype "bidirectional"))
      (node (ref "J10") (pin "2") (pinfunction "2_2") (pintype "passive"))
    )
    (net (code "5") (name "/ANALOG2") (class "Default")
      (node (ref "IC3") (pin "24") (pinfunction "PA1_24") (pintype "bidirectional"))
      (node (ref "J10") (pin "3") (pinfunction "3_3") (pintype "passive"))
    )
    (net (code "6") (name "/ANALOG3") (class "Default")
      (node (ref "IC3") (pin "23") (pinfunction "PA0_23") (pintype "bidirectional"))
      (node (ref "J10") (pin "4") (pinfunction "4_4") (pintype "passive"))
    )
    (net (code "7") (name "/ANALOG4") (class "Default")
      (node (ref "IC3") (pin "18") (pinfunction "PC3_18") (pintype "bidirectional"))
      (node (ref "J10") (pin "5") (pinfunction "5_5") (pintype "passive"))
    )
    (net (code "8") (name "/ANALOG5") (class "Default")
      (node (ref "IC3") (pin "17") (pinfunction "PC2_17") (pintype "bidirectional"))
      (node (ref "J10") (pin "6") (pinfunction "6_6") (pintype "passive"))
    )
    (net (code "9") (name "/ANALOG6") (class "Default")
      (node (ref "IC3") (pin "16") (pinfunction "PC1_16") (pintype "bidirectional"))
      (node (ref "J10") (pin "7") (pinfunction "7_7") (pintype "passive"))
    )
    (net (code "10") (name "/ANALOG7") (class "Default")
      (node (ref "IC3") (pin "15") (pinfunction "PC0_15") (pintype "bidirectional"))
      (node (ref "J10") (pin "8") (pinfunction "8_8") (pintype "passive"))
    )
    (net (code "11") (name "/ANALOG8") (class "Default")
      (node (ref "IC3") (pin "36") (pinfunction "PB1_36") (pintype "bidirectional"))
      (node (ref "JP3") (pin "3") (pinfunction "3_3") (pintype "passive"))
    )
    (net (code "12") (name "/ANALOG9") (class "Default")
      (node (ref "IC3") (pin "35") (pinfunction "PB0_35") (pintype "bidirectional"))
      (node (ref "JP3") (pin "4") (pinfunction "4_4") (pintype "passive"))
    )
    (net (code "13") (name "/BAT_SENSE") (class "Default")
      (node (ref "IC3") (pin "33") (pinfunction "PC4_33") (pintype "bidirectional"))
      (node (ref "R18") (pin "2") (pinfunction "2_2") (pintype "passive"))
      (node (ref "R19") (pin "1") (pinfunction "1_1") (pintype "passive"))
    )
    (net (code "14") (name "/BOOT1") (class "Default")
      (node (ref "IC3") (pin "37") (pinfunction "PB2_37") (pintype "bidirectional"))
      (node (ref "R43") (pin "2") (pinfunction "2_2") (pintype "passive"))
    )
    (net (code "15") (name "/BTN0") (class "Default")
      (node (ref "BTN0") (pin "1") (pinfunction "S_1") (pintype "passive"))
      (node (ref "BTN0") (pin "2") (pinfunction "S1_2") (pintype "passive"))
      (node (ref "IC3") (pin "57") (pinfunction "PD10_57") (pintype "bidirectional"))
    )
    (net (code "16") (name "/BTN1") (class "Default")
      (node (ref "BTN1") (pin "1") (pinfunction "S_1") (pintype "passive"))
      (node (ref "BTN1") (pin "2") (pinfunction "S1_2") (pintype "passive"))
      (node (ref "IC3") (pin "58") (pinfunction "PD11_58") (pintype "bidirectional"))
    )
    (net (code "17") (name "/BUZZER") (class "Default")
      (node (ref "IC3") (pin "29") (pinfunction "PA4_29") (pintype "bidirectional"))
      (node (ref "R39") (pin "1") (pinfunction "1_1") (pintype "passive"))
    )
    (net (code "18") (name "/DIGITAL0") (class "Default")
      (node (ref "IC3") (pin "9") (pinfunction "PC15_9") (pintype "bidirectional"))
      (node (ref "J13") (pin "1") (pinfunction "1_1") (pintype "passive"))
    )
    (net (code "19") (name "/DIGITAL1") (class "Default")
      (node (ref "IC3") (pin "8") (pinfunction "PC14_8") (pintype "bidirectional"))
      (node (ref "J13") (pin "2") (pinfunction "2_2") (pintype "passive"))
    )
    (net (code "20") (name "/DIGITAL2") (class "Default")
      (node (ref "IC3") (pin "7") (pinfunction "PC13_7") (pintype "bidirectional"))
      (node (ref "J13") (pin "3") (pinfunction "3_3") (pintype "passive"))
    )
    (net (code "21") (name "/DIGITAL3") (class "Default")
      (node (ref "IC3") (pin "5") (pinfunction "PE6_5") (pintype "bidirectional"))
      (node (ref "J13") (pin "4") (pinfunction "4_4") (pintype "passive"))
    )
    (net (code "22") (name "/DIGITAL4") (class "Default")
      (node (ref "IC3") (pin "4") (pinfunction "PE5_4") (pintype "bidirectional"))
      (node (ref "J13") (pin "5") (pinfunction "5_5") (pintype "passive"))
    )
    (net (code "23") (name "/DIGITAL5") (class "Default")
      (node (ref "IC3") (pin "3") (pinfunction "PE4_3") (pintype "bidirectional"))
      (node (ref "J13") (pin "6") (pinfunction "6_6") (pintype "passive"))
    )
    (net (code "24") (name "/DIGITAL6") (class "Default")
      (node (ref "IC3") (pin "2") (pinfunction "PE3_2") (pintype "bidirectional"))
      (node (ref "J13") (pin "7") (pinfunction "7_7") (pintype "passive"))
    )
    (net (code "25") (name "/DIGITAL7") (class "Default")
      (node (ref "IC3") (pin "1") (pinfunction "PE2_1") (pintype "bidirectional"))
      (node (ref "J13") (pin "8") (pinfunction "8_8") (pintype "passive"))
    )
    (net (code "26") (name "/DIGITAL8") (class "Default")
      (node (ref "IC3") (pin "98") (pinfunction "PE1_98") (pintype "bidirectional"))
      (node (ref "J13") (pin "9") (pinfunction "9_9") (pintype "passive"))
    )
    (net (code "27") (name "/DIGITAL9") (class "Default")
      (node (ref "IC3") (pin "97") (pinfunction "PE0_97") (pintype "bidirectional"))
      (node (ref "J13") (pin "10") (pinfunction "10_10") (pintype "passive"))
    )
    (net (code "28") (name "/DIGITAL10") (class "Default")
      (node (ref "IC3") (pin "91") (pinfunction "PB5_91") (pintype "bidirectional"))
      (node (ref "J13") (pin "11") (pinfunction "11_11") (pintype "passive"))
    )
    (net (code "29") (name "/DIGITAL11") (class "Default")
      (node (ref "IC3") (pin "90") (pinfunction "PB4_90") (pintype "bidirectional"))
      (node (ref "J13") (pin "12") (pinfunction "12_12") (pintype "passive"))
    )
    (net (code "30") (name "/DIGITAL12") (class "Default")
      (node (ref "IC3") (pin "89") (pinfunction "PB3_89") (pintype "bidirectional"))
      (node (ref "J13") (pin "13") (pinfunction "13_13") (pintype "passive"))
    )
    (net (code "31") (name "/DIGITAL13") (class "Default")
      (node (ref "IC3") (pin "88") (pinfunction "PD7_88") (pintype "bidirectional"))
      (node (ref "J13") (pin "14") (pinfunction "14_14") (pintype "passive"))
    )
    (net (code "32") (name "/DIGITAL14") (class "Default")
      (node (ref "IC3") (pin "84") (pinfunction "PD3_84") (pintype "bidirectional"))
      (node (ref "J13") (pin "15") (pinfunction "15_15") (pintype "passive"))
    )
    (net (code "33") (name "/DIGITAL15") (class "Default")
      (node (ref "IC3") (pin "44") (pinfunction "PE13_44") (pintype "bidirectional"))
      (node (ref "JP3") (pin "1") (pinfunction "1_1") (pintype "passive"))
    )
    (net (code "34") (name "/DIGITAL16") (class "Default")
      (node (ref "IC3") (pin "45") (pinfunction "PE14_45") (pintype "bidirectional"))
      (node (ref "JP3") (pin "2") (pinfunction "2_2") (pintype "passive"))
    )
    (net (code "35") (name "/I2C1_SCL") (class "Default")
      (node (ref "IC3") (pin "95") (pinfunction "PB8_95") (pintype "bidirectional"))
      (node (ref "JP1") (pin "1") (pinfunction "1_1") (pintype "passive"))
      (node (ref "R23") (pin "1") (pinfunction "1_1") (pintype "passive"))
      (node (ref "U$1") (pin "24") (pinfunction "SCL_24") (pintype "bidirectional"))
    )
    (net (code "36") (name "/I2C1_SDA") (class "Default")
      (node (ref "IC3") (pin "96") (pinfunction "PB9_96") (pintype "bidirectional"))
      (node (ref "JP1") (pin "2") (pinfunction "2_2") (pintype "passive"))
      (node (ref "R22") (pin "1") (pinfunction "1_1") (pintype "passive"))
      (node (ref "U$1") (pin "28") (pinfunction "SDA_28") (pintype "bidirectional"))
    )
    (net (code "37") (name "/I2C2_SCL{slash}USART3_TX") (class "Default")
      (node (ref "IC3") (pin "47") (pinfunction "PB10_47") (pintype "bidirectional"))
      (node (ref "J1") (pin "1") (pinfunction "1_1") (pintype "passive"))
      (node (ref "J2") (pin "1") (pinfunction "1_1") (pintype "passive"))
      (node (ref "R25") (pin "1") (pinfunction "1_1") (pintype "passive"))
      (node (ref "XB1") (pin "3") (pinfunction "DIN/~{CONFIG}_3") (pintype "input"))
    )
    (net (code "38") (name "/I2C2_SDA{slash}USART3_RX") (class "Default")
      (node (ref "IC3") (pin "48") (pinfunction "PB11_48") (pintype "bidirectional"))
      (node (ref "J1") (pin "2") (pinfunction "2_2") (pintype "passive"))
      (node (ref "J2") (pin "2") (pinfunction "2_2") (pintype "passive"))
      (node (ref "R24") (pin "1") (pinfunction "1_1") (pintype "passive"))
      (node (ref "XB1") (pin "2") (pinfunction "DOUT_2") (pintype "output"))
    )
    (net (code "39") (name "/LCD_CLK") (class "Default")
      (node (ref "IC3") (pin "69") (pinfunction "PA10_69") (pintype "bidirectional"))
      (node (ref "U$3") (pin "8") (pinfunction "CLK_8") (pintype "bidirectional"))
    )
    (net (code "40") (name "/LCD_DATA") (class "Default")
      (node (ref "IC3") (pin "67") (pinfunction "PA8_67") (pintype "bidirectional"))
      (node (ref "U$3") (pin "1") (pinfunction "A1_1") (pintype "bidirectional"))
      (node (ref "U$3") (pin "2") (pinfunction "A2_2") (pintype "bidirectional"))
    )
    (net (code "41") (name "/LCD_E") (class "Default")
      (node (ref "IC3") (pin "81") (pinfunction "PD0_81") (pintype "bidirectional"))
      (node (ref "LCD") (pin "E") (pinfunction "E_E") (pintype "bidirectional"))
    )
    (net (code "42") (name "/LCD_RS") (class "Default")
      (node (ref "IC3") (pin "82") (pinfunction "PD1_82") (pintype "bidirectional"))
      (node (ref "LCD") (pin "RS") (pinfunction "RS_RS") (pintype "bidirectional"))
    )
    (net (code "43") (name "/LED0") (class "Default")
      (node (ref "IC3") (pin "46") (pinfunction "PE15_46") (pintype "bidirectional"))
      (node (ref "R20") (pin "2") (pinfunction "2_2") (pintype "passive"))
    )
    (net (code "44") (name "/LED1") (class "Default")
      (node (ref "IC3") (pin "85") (pinfunction "PD4_85") (pintype "bidirectional"))
      (node (ref "R21") (pin "2") (pinfunction "2_2") (pintype "passive"))
    )
    (net (code "45") (name "/M0_A") (class "Default")
      (node (ref "IC3") (pin "38") (pinfunction "PE7_38") (pintype "bidirectional"))
      (node (ref "U$5") (pin "17") (pinfunction "IN1B_17") (pintype "bidirectional"))
      (node (ref "U$5") (pin "43") (pinfunction "IN1A_43") (pintype "bidirectional"))
    )
    (net (code "46") (name "/M0_B") (class "Default")
      (node (ref "IC3") (pin "39") (pinfunction "PE8_39") (pintype "bidirectional"))
      (node (ref "U$5") (pin "18") (pinfunction "IN2B_18") (pintype "bidirectional"))
      (node (ref "U$5") (pin "44") (pinfunction "IN2A_44") (pintype "bidirectional"))
    )
    (net (code "47") (name "/M0_EN") (class "Default")
      (node (ref "IC3") (pin "40") (pinfunction "PE9_40") (pintype "bidirectional"))
      (node (ref "U$5") (pin "20") (pinfunction "ENB_20") (pintype "bidirectional"))
      (node (ref "U$5") (pin "41") (pinfunction "ENA_41") (pintype "bidirectional"))
    )
    (net (code "48") (name "/M0_FAULT") (class "Default")
      (node (ref "IC3") (pin "55") (pinfunction "PD8_55") (pintype "bidirectional"))
      (node (ref "U$5") (pin "13") (pinfunction "FAULT_B_13") (pintype "bidirectional"))
      (node (ref "U$5") (pin "48") (pinfunction "FAULT_A_48") (pintype "bidirectional"))
    )
    (net (code "49") (name "/M1_A") (class "Default")
      (node (ref "IC3") (pin "41") (pinfunction "PE10_41") (pintype "bidirectional"))
      (node (ref "U$4") (pin "17") (pinfunction "IN1B_17") (pintype "bidirectional"))
      (node (ref "U$4") (pin "43") (pinfunction "IN1A_43") (pintype "bidirectional"))
    )
    (net (code "50") (name "/M1_B") (class "Default")
      (node (ref "IC3") (pin "43") (pinfunction "PE12_43") (pintype "bidirectional"))
      (node (ref "U$4") (pin "18") (pinfunction "IN2B_18") (pintype "bidirectional"))
      (node (ref "U$4") (pin "44") (pinfunction "IN2A_44") (pintype "bidirectional"))
    )
    (net (code "51") (name "/M1_EN") (class "Default")
      (node (ref "IC3") (pin "42") (pinfunction "PE11_42") (pintype "bidirectional"))
      (node (ref "U$4") (pin "20") (pinfunction "ENB_20") (pintype "bidirectional"))
      (node (ref "U$4") (pin "41") (pinfunction "ENA_41") (pintype "bidirectional"))
    )
    (net (code "52") (name "/M1_FAULT") (class "Default")
      (node (ref "IC3") (pin "56") (pinfunction "PD9_56") (pintype "bidirectional"))
      (node (ref "U$4") (pin "13") (pinfunction "FAULT_B_13") (pintype "bidirectional"))
      (node (ref "U$4") (pin "48") (pinfunction "FAULT_A_48") (pintype "bidirectional"))
    )
    (net (code "53") (name "/MPOWER") (class "Default")
      (node (ref "C11") (pin "1") (pinfunction "1_1") (pintype "passive"))
      (node (ref "C20") (pin "1") (pinfunction "1_1") (pintype "passive"))
      (node (ref "C26") (pin "1") (pinfunction "1_1") (pintype "passive"))
      (node (ref "C28") (pin "1") (pinfunction "1_1") (pintype "passive"))
      (node (ref "C31") (pin "1") (pinfunction "1_1") (pintype "passive"))
      (node (ref "C48") (pin "1") (pinfunction "1_1") (pintype "passive"))
      (node (ref "C8") (pin "+") (pinfunction "+_+") (pintype "passive"))
      (node (ref "C9") (pin "1") (pinfunction "1_1") (pintype "passive"))
      (node (ref "JP3") (pin "8") (pinfunction "8_8") (pintype "passive"))
      (node (ref "R10") (pin "2") (pinfunction "2_2") (pintype "passive"))
      (node (ref "R18") (pin "1") (pinfunction "1_1") (pintype "passive"))
      (node (ref "R34") (pin "2") (pinfunction "2_2") (pintype "passive"))
      (node (ref "U$10") (pin "1") (pinfunction "1_1") (pintype "bidirectional"))
      (node (ref "U$11") (pin "1") (pinfunction "1_1") (pintype "bidirectional"))
      (node (ref "U$4") (pin "26") (pinfunction "VS_26") (pintype "bidirectional"))
      (node (ref "U$4") (pin "27") (pinfunction "VS_27") (pintype "bidirectional"))
      (node (ref "U$4") (pin "34") (pinfunction "VS_34") (pintype "bidirectional"))
      (node (ref "U$4") (pin "35") (pinfunction "VS_35") (pintype "bidirectional"))
      (node (ref "U$5") (pin "26") (pinfunction "VS_26") (pintype "bidirectional"))
      (node (ref "U$5") (pin "27") (pinfunction "VS_27") (pintype "bidirectional"))
      (node (ref "U$5") (pin "34") (pinfunction "VS_34") (pintype "bidirectional"))
      (node (ref "U$5") (pin "35") (pinfunction "VS_35") (pintype "bidirectional"))
      (node (ref "U$7") (pin "5") (pinfunction "D_5") (pintype "bidirectional"))
      (node (ref "U$7") (pin "6") (pinfunction "D_6") (pintype "bidirectional"))
      (node (ref "U$7") (pin "7") (pinfunction "D_7") (pintype "bidirectional"))
      (node (ref "U$7") (pin "8") (pinfunction "D_8") (pintype "bidirectional"))
      (node (ref "U$7") (pin "PAD") (pinfunction "D_PAD") (pintype "bidirectional"))
      (node (ref "U2") (pin "4") (pinfunction "VIN_4") (pintype "bidirectional"))
      (node (ref "U2") (pin "5") (pinfunction "VIN_5") (pintype "bidirectional"))
      (node (ref "U2") (pin "6") (pinfunction "VIN_6") (pintype "bidirectional"))
    )
    (net (code "54") (name "/OUT1") (class "Default")
      (node (ref "LED6") (pin "2") (pinfunction "2_2") (pintype "passive"))
      (node (ref "LED6") (pin "3") (pinfunction "3_3") (pintype "passive"))
      (node (ref "MOTOR1") (pin "L") (pinfunction "L_L") (pintype "bidirectional"))
      (node (ref "U$5") (pin "10") (pinfunction "OUT1B_10") (pintype "bidirectional"))
      (node (ref "U$5") (pin "11") (pinfunction "OUT1B_11") (pintype "bidirectional"))
      (node (ref "U$5") (pin "2") (pinfunction "OUT1A_2") (pintype "bidirectional"))
      (node (ref "U$5") (pin "3") (pinfunction "OUT1A_3") (pintype "bidirectional"))
    )
    (net (code "55") (name "/OUT2") (class "Default")
      (node (ref "MOTOR1") (pin "R") (pinfunction "R_R") (pintype "bidirectional"))
      (node (ref "R37") (pin "1") (pinfunction "1_1") (pintype "passive"))
      (node (ref "U$5") (pin "22") (pinfunction "OUT2B_22") (pintype "bidirectional"))
      (node (ref "U$5") (pin "23") (pinfunction "OUT2B_23") (pintype "bidirectional"))
      (node (ref "U$5") (pin "38") (pinfunction "OUT2A_38") (pintype "bidirectional"))
      (node (ref "U$5") (pin "39") (pinfunction "OUT2A_39") (pintype "bidirectional"))
    )
    (net (code "56") (name "/OUT3") (class "Default")
      (node (ref "LED7") (pin "2") (pinfunction "2_2") (pintype "passive"))
      (node (ref "LED7") (pin "3") (pinfunction "3_3") (pintype "passive"))
      (node (ref "MOTOR0") (pin "L") (pinfunction "L_L") (pintype "bidirectional"))
      (node (ref "U$4") (pin "10") (pinfunction "OUT1B_10") (pintype "bidirectional"))
      (node (ref "U$4") (pin "11") (pinfunction "OUT1B_11") (pintype "bidirectional"))
      (node (ref "U$4") (pin "2") (pinfunction "OUT1A_2") (pintype "bidirectional"))
      (node (ref "U$4") (pin "3") (pinfunction "OUT1A_3") (pintype "bidirectional"))
    )
    (net (code "57") (name "/OUT4") (class "Default")
      (node (ref "MOTOR0") (pin "R") (pinfunction "R_R") (pintype "bidirectional"))
      (node (ref "R38") (pin "1") (pinfunction "1_1") (pintype "passive"))
      (node (ref "U$4") (pin "22") (pinfunction "OUT2B_22") (pintype "bidirectional"))
      (node (ref "U$4") (pin "23") (pinfunction "OUT2B_23") (pintype "bidirectional"))
      (node (ref "U$4") (pin "38") (pinfunction "OUT2A_38") (pintype "bidirectional"))
      (node (ref "U$4") (pin "39") (pinfunction "OUT2A_39") (pintype "bidirectional"))
    )
    (net (code "58") (name "/RAW_SPWR") (class "Default")
      (node (ref "C27") (pin "1") (pinfunction "1_1") (pintype "passive"))
      (node (ref "R29") (pin "1") (pinfunction "1_1") (pintype "passive"))
      (node (ref "R36") (pin "2") (pinfunction "2_2") (pintype "passive"))
      (node (ref "SERVO_PWR") (pin "L") (pinfunction "L_L") (pintype "bidirectional"))
      (node (ref "U$8") (pin "5") (pinfunction "D_5") (pintype "bidirectional"))
      (node (ref "U$8") (pin "6") (pinfunction "D_6") (pintype "bidirectional"))
      (node (ref "U$8") (pin "7") (pinfunction "D_7") (pintype "bidirectional"))
      (node (ref "U$8") (pin "8") (pinfunction "D_8") (pintype "bidirectional"))
      (node (ref "U$8") (pin "PAD") (pinfunction "D_PAD") (pintype "bidirectional"))
      (node (ref "U$9") (pin "4") (pinfunction "G_4") (pintype "bidirectional"))
    )
    (net (code "59") (name "/RESET") (class "Default")
      (node (ref "C30") (pin "2") (pinfunction "2_2") (pintype "passive"))
      (node (ref "IC3") (pin "14") (pinfunction "NRST_14") (pintype "input"))
      (node (ref "JP3") (pin "5") (pinfunction "5_5") (pintype "passive"))
      (node (ref "R7") (pin "1") (pinfunction "1_1") (pintype "passive"))
      (node (ref "RESET") (pin "1") (pinfunction "S_1") (pintype "passive"))
      (node (ref "RESET") (pin "2") (pinfunction "S1_2") (pintype "passive"))
    )
    (net (code "60") (name "/SERVO0") (class "Default")
      (node (ref "IC3") (pin "59") (pinfunction "PD12_59") (pintype "bidirectional"))
      (node (ref "J16") (pin "8") (pinfunction "8_8") (pintype "passive"))
    )
    (net (code "61") (name "/SERVO1") (class "Default")
      (node (ref "IC3") (pin "60") (pinfunction "PD13_60") (pintype "bidirectional"))
      (node (ref "J16") (pin "7") (pinfunction "7_7") (pintype "passive"))
    )
    (net (code "62") (name "/SERVO2") (class "Default")
      (node (ref "IC3") (pin "61") (pinfunction "PD14_61") (pintype "bidirectional"))
      (node (ref "J16") (pin "6") (pinfunction "6_6") (pintype "passive"))
    )
    (net (code "63") (name "/SERVO3") (class "Default")
      (node (ref "IC3") (pin "62") (pinfunction "PD15_62") (pintype "bidirectional"))
      (node (ref "J16") (pin "5") (pinfunction "5_5") (pintype "passive"))
    )
    (net (code "64") (name "/SERVO4") (class "Default")
      (node (ref "IC3") (pin "63") (pinfunction "PC6_63") (pintype "bidirectional"))
      (node (ref "J16") (pin "4") (pinfunction "4_4") (pintype "passive"))
    )
    (net (code "65") (name "/SERVO5") (class "Default")
      (node (ref "IC3") (pin "64") (pinfunction "PC7_64") (pintype "bidirectional"))
      (node (ref "J16") (pin "3") (pinfunction "3_3") (pintype "passive"))
    )
    (net (code "66") (name "/SERVO6") (class "Default")
      (node (ref "IC3") (pin "65") (pinfunction "PC8_65") (pintype "bidirectional"))
      (node (ref "J16") (pin "2") (pinfunction "2_2") (pintype "passive"))
    )
    (net (code "67") (name "/SERVO7") (class "Default")
      (node (ref "IC3") (pin "66") (pinfunction "PC9_66") (pintype "bidirectional"))
      (node (ref "J16") (pin "1") (pinfunction "1_1") (pintype "passive"))
    )
    (net (code "68") (name "/SERVO_SENSE") (class "Default")
      (node (ref "IC3") (pin "34") (pinfunction "PC5_34") (pintype "bidirectional"))
      (node (ref "R40") (pin "2") (pinfunction "2_2") (pintype "passive"))
      (node (ref "R41") (pin "1") (pinfunction "1_1") (pintype "passive"))
    )
    (net (code "69") (name "/SPI1_MISO") (class "Default")
      (node (ref "IC3") (pin "31") (pinfunction "PA6_31") (pintype "bidirectional"))
      (node (ref "J5") (pin "4") (pinfunction "4_4") (pintype "passive"))
    )
    (net (code "70") (name "/SPI1_MOSI") (class "Default")
      (node (ref "IC3") (pin "32") (pinfunction "PA7_32") (pintype "bidirectional"))
      (node (ref "J5") (pin "3") (pinfunction "3_3") (pintype "passive"))
    )
    (net (code "71") (name "/SPI1_NSS") (class "Default")
      (node (ref "IC3") (pin "77") (pinfunction "PA15_77") (pintype "bidirectional"))
      (node (ref "J5") (pin "6") (pinfunction "6_6") (pintype "passive"))
    )
    (net (code "72") (name "/SPI1_SCK") (class "Default")
      (node (ref "IC3") (pin "30") (pinfunction "PA5_30") (pintype "bidirectional"))
      (node (ref "J5") (pin "5") (pinfunction "5_5") (pintype "passive"))
    )
    (net (code "73") (name "/SPI3_MISO") (class "Default")
      (node (ref "IC3") (pin "79") (pinfunction "PC11_79") (pintype "bidirectional"))
      (node (ref "SD") (pin "7") (pinfunction "DO_7") (pintype "bidirectional"))
    )
    (net (code "74") (name "/SPI3_MOSI") (class "Default")
      (node (ref "IC3") (pin "80") (pinfunction "PC12_80") (pintype "bidirectional"))
      (node (ref "SD") (pin "3") (pinfunction "DI_3") (pintype "bidirectional"))
    )
    (net (code "75") (name "/SPI3_NSS") (class "Default")
      (node (ref "IC3") (pin "83") (pinfunction "PD2_83") (pintype "bidirectional"))
      (node (ref "SD") (pin "2") (pinfunction "CS_2") (pintype "bidirectional"))
    )
    (net (code "76") (name "/SPI3_SCK") (class "Default")
      (node (ref "IC3") (pin "78") (pinfunction "PC10_78") (pintype "bidirectional"))
      (node (ref "SD") (pin "5") (pinfunction "SCK_5") (pintype "bidirectional"))
    )
    (net (code "77") (name "/SPWR") (class "Default")
      (node (ref "J15") (pin "1") (pinfunction "1_1") (pintype "passive"))
      (node (ref "J15") (pin "2") (pinfunction "2_2") (pintype "passive"))
      (node (ref "J15") (pin "3") (pinfunction "3_3") (pintype "passive"))
      (node (ref "J15") (pin "4") (pinfunction "4_4") (pintype "passive"))
      (node (ref "J15") (pin "5") (pinfunction "5_5") (pintype "passive"))
      (node (ref "J15") (pin "6") (pinfunction "6_6") (pintype "passive"))
      (node (ref "J15") (pin "7") (pinfunction "7_7") (pintype "passive"))
      (node (ref "J15") (pin "8") (pinfunction "8_8") (pintype "passive"))
      (node (ref "R40") (pin "1") (pinfunction "1_1") (pintype "passive"))
      (node (ref "U$8") (pin "1") (pinfunction "S_1") (pintype "bidirectional"))
      (node (ref "U$8") (pin "2") (pinfunction "S_2") (pintype "bidirectional"))
      (node (ref "U$8") (pin "3") (pinfunction "S_3") (pintype "bidirectional"))
      (node (ref "U$9") (pin "1") (pinfunction "S_1") (pintype "bidirectional"))
      (node (ref "U$9") (pin "2") (pinfunction "S_2") (pintype "bidirectional"))
      (node (ref "U$9") (pin "3") (pinfunction "S_3") (pintype "bidirectional"))
    )
    (net (code "78") (name "/SWDCLK") (class "Default")
      (node (ref "IC3") (pin "76") (pinfunction "PA14_76") (pintype "bidirectional"))
      (node (ref "J7") (pin "2") (pinfunction "2_2") (pintype "passive"))
    )
    (net (code "79") (name "/SWDIO") (class "Default")
      (node (ref "IC3") (pin "72") (pinfunction "PA13_72") (pintype "bidirectional"))
      (node (ref "J7") (pin "1") (pinfunction "1_1") (pintype "passive"))
    )
    (net (code "80") (name "/USART1_RX") (class "Default")
      (node (ref "IC3") (pin "93") (pinfunction "PB7_93") (pintype "bidirectional"))
      (node (ref "J6") (pin "3") (pinfunction "3_3") (pintype "passive"))
    )
    (net (code "81") (name "/USART1_TX") (class "Default")
      (node (ref "IC3") (pin "92") (pinfunction "PB6_92") (pintype "bidirectional"))
      (node (ref "J6") (pin "2") (pinfunction "2_2") (pintype "passive"))
    )
    (net (code "82") (name "/USART2_RX") (class "Default")
      (node (ref "IC3") (pin "87") (pinfunction "PD6_87") (pintype "bidirectional"))
      (node (ref "J3") (pin "2") (pinfunction "2_2") (pintype "passive"))
    )
    (net (code "83") (name "/USART2_TX") (class "Default")
      (node (ref "IC3") (pin "86") (pinfunction "PD5_86") (pintype "bidirectional"))
      (node (ref "J3") (pin "1") (pinfunction "1_1") (pintype "passive"))
    )
    (net (code "84") (name "/USB_5V") (class "Default")
      (node (ref "C22") (pin "2") (pinfunction "2_2") (pintype "passive"))
      (node (ref "C24") (pin "2") (pinfunction "2_2") (pintype "passive"))
      (node (ref "IC3") (pin "68") (pinfunction "PA9_68") (pintype "bidirectional"))
      (node (ref "Q1") (pin "1") (pinfunction "D_1") (pintype "bidirectional"))
      (node (ref "Q1") (pin "2") (pinfunction "D_2") (pintype "bidirectional"))
      (node (ref "Q1") (pin "5") (pinfunction "D_5") (pintype "bidirectional"))
      (node (ref "Q1") (pin "6") (pinfunction "D_6") (pintype "bidirectional"))
      (node (ref "Q1") (pin "8") (pinfunction "D_8") (pintype "bidirectional"))
      (node (ref "USB2") (pin "VBUS") (pinfunction "VBUS_VBUS") (pintype "bidirectional"))
    )
    (net (code "85") (name "/USB_DEV_DM") (class "Default")
      (node (ref "C14") (pin "1") (pinfunction "1_1") (pintype "passive"))
      (node (ref "IC3") (pin "70") (pinfunction "PA11_70") (pintype "bidirectional"))
      (node (ref "R46") (pin "2") (pinfunction "2_2") (pintype "passive"))
    )
    (net (code "86") (name "/USB_DEV_DP") (class "Default")
      (node (ref "C13") (pin "1") (pinfunction "1_1") (pintype "passive"))
      (node (ref "IC3") (pin "71") (pinfunction "PA12_71") (pintype "bidirectional"))
      (node (ref "R47") (pin "2") (pinfunction "2_2") (pintype "passive"))
    )
    (net (code "87") (name "/USB_HOST_DM") (class "Default")
      (node (ref "C18") (pin "1") (pinfunction "1_1") (pintype "passive"))
      (node (ref "IC3") (pin "53") (pinfunction "PB14_53") (pintype "bidirectional"))
      (node (ref "R49") (pin "2") (pinfunction "2_2") (pintype "passive"))
    )
    (net (code "88") (name "/USB_HOST_DP") (class "Default")
      (node (ref "C17") (pin "1") (pinfunction "1_1") (pintype "passive"))
      (node (ref "IC3") (pin "54") (pinfunction "PB15_54") (pintype "bidirectional"))
      (node (ref "R48") (pin "2") (pinfunction "2_2") (pintype "passive"))
    )
    (net (code "89") (name "/USB_HOST_EN") (class "Default")
      (node (ref "IC3") (pin "52") (pinfunction "PB13_52") (pintype "bidirectional"))
      (node (ref "U$2") (pin "4") (pinfunction "EN_4") (pintype "bidirectional"))
    )
    (net (code "90") (name "/USB_HOST_FAULT") (class "Default")
      (node (ref "IC3") (pin "51") (pinfunction "PB12_51") (pintype "bidirectional"))
      (node (ref "U$2") (pin "5") (pinfunction "FAULT_5") (pintype "bidirectional"))
    )
    (net (code "91") (name "GND") (class "Default")
      (node (ref "BTN0") (pin "3") (pinfunction "P_3") (pintype "passive"))
      (node (ref "BTN0") (pin "4") (pinfunction "P1_4") (pintype "passive"))
      (node (ref "BTN1") (pin "3") (pinfunction "P_3") (pintype "passive"))
      (node (ref "BTN1") (pin "4") (pinfunction "P1_4") (pintype "passive"))
      (node (ref "C1") (pin "2") (pinfunction "2_2") (pintype "passive"))
      (node (ref "C10") (pin "2") (pinfunction "2_2") (pintype "passive"))
      (node (ref "C11") (pin "2") (pinfunction "2_2") (pintype "passive"))
      (node (ref "C12") (pin "2") (pinfunction "2_2") (pintype "passive"))
      (node (ref "C13") (pin "2") (pinfunction "2_2") (pintype "passive"))
      (node (ref "C14") (pin "2") (pinfunction "2_2") (pintype "passive"))
      (node (ref "C15") (pin "2") (pinfunction "2_2") (pintype "passive"))
      (node (ref "C16") (pin "2") (pinfunction "2_2") (pintype "passive"))
      (node (ref "C17") (pin "2") (pinfunction "2_2") (pintype "passive"))
      (node (ref "C18") (pin "2") (pinfunction "2_2") (pintype "passive"))
      (node (ref "C19") (pin "2") (pinfunction "2_2") (pintype "passive"))
      (node (ref "C2") (pin "2") (pinfunction "2_2") (pintype "passive"))
      (node (ref "C21") (pin "2") (pinfunction "2_2") (pintype "passive"))
      (node (ref "C22") (pin "1") (pinfunction "1_1") (pintype "passive"))
      (node (ref "C23") (pin "2") (pinfunction "2_2") (pintype "passive"))
      (node (ref "C24") (pin "1") (pinfunction "1_1") (pintype "passive"))
      (node (ref "C25") (pin "2") (pinfunction "2_2") (pintype "passive"))
      (node (ref "C26") (pin "2") (pinfunction "2_2") (pintype "passive"))
      (node (ref "C27") (pin "2") (pinfunction "2_2") (pintype "passive"))
      (node (ref "C28") (pin "2") (pinfunction "2_2") (pintype "passive"))
      (node (ref "C3") (pin "2") (pinfunction "2_2") (pintype "passive"))
      (node (ref "C31") (pin "2") (pinfunction "2_2") (pintype "passive"))
      (node (ref "C33") (pin "1") (pinfunction "1_1") (pintype "passive"))
      (node (ref "C34") (pin "2") (pinfunction "2_2") (pintype "passive"))
      (node (ref "C35") (pin "2") (pinfunction "2_2") (pintype "passive"))
      (node (ref "C36") (pin "2") (pinfunction "2_2") (pintype "passive"))
      (node (ref "C37") (pin "2") (pinfunction "2_2") (pintype "passive"))
      (node (ref "C39") (pin "2") (pinfunction "2_2") (pintype "passive"))
      (node (ref "C4") (pin "2") (pinfunction "2_2") (pintype "passive"))
      (node (ref "C40") (pin "2") (pinfunction "2_2") (pintype "passive"))
      (node (ref "C41") (pin "2") (pinfunction "2_2") (pintype "passive"))
      (node (ref "C42") (pin "2") (pinfunction "2_2") (pintype "passive"))
      (node (ref "C43") (pin "2") (pinfunction "2_2") (pintype "passive"))
      (node (ref "C44") (pin "-") (pinfunction "-_-") (pintype "passive"))
      (node (ref "C46") (pin "2") (pinfunction "2_2") (pintype "passive"))
      (node (ref "C47") (pin "2") (pinfunction "2_2") (pintype "passive"))
      (node (ref "C5") (pin "2") (pinfunction "2_2") (pintype "passive"))
      (node (ref "C50") (pin "2") (pinfunction "2_2") (pintype "passive"))
      (node (ref "C6") (pin "2") (pinfunction "2_2") (pintype "passive"))
      (node (ref "C7") (pin "2") (pinfunction "2_2") (pintype "passive"))
      (node (ref "C8") (pin "-") (pinfunction "-_-") (pintype "passive"))
      (node (ref "C9") (pin "2") (pinfunction "2_2") (pintype "passive"))
      (node (ref "IC3") (pin "10") (pinfunction "VSS_5_10") (pintype "power_in"))
      (node (ref "IC3") (pin "20") (pinfunction "VSSA_20") (pintype "power_in"))
      (node (ref "IC3") (pin "27") (pinfunction "VSS_4_27") (pintype "power_in"))
      (node (ref "IC3") (pin "74") (pinfunction "VSS_2_74") (pintype "power_in"))
      (node (ref "IC3") (pin "99") (pinfunction "VSS_6_99") (pintype "power_in"))
      (node (ref "IC4") (pin "4") (pinfunction "V-_4") (pintype "power_in"))
      (node (ref "J1") (pin "3") (pinfunction "3_3") (pintype "passive"))
      (node (ref "J11") (pin "1") (pinfunction "1_1") (pintype "passive"))
      (node (ref "J11") (pin "10") (pinfunction "10_10") (pintype "passive"))
      (node (ref "J11") (pin "11") (pinfunction "11_11") (pintype "passive"))
      (node (ref "J11") (pin "12") (pinfunction "12_12") (pintype "passive"))
      (node (ref "J11") (pin "13") (pinfunction "13_13") (pintype "passive"))
      (node (ref "J11") (pin "14") (pinfunction "14_14") (pintype "passive"))
      (node (ref "J11") (pin "15") (pinfunction "15_15") (pintype "passive"))
      (node (ref "J11") (pin "2") (pinfunction "2_2") (pintype "passive"))
      (node (ref "J11") (pin "3") (pinfunction "3_3") (pintype "passive"))
      (node (ref "J11") (pin "4") (pinfunction "4_4") (pintype "passive"))
      (node (ref "J11") (pin "5") (pinfunction "5_5") (pintype "passive"))
      (node (ref "J11") (pin "6") (pinfunction "6_6") (pintype "passive"))
      (node (ref "J11") (pin "7") (pinfunction "7_7") (pintype "passive"))
      (node (ref "J11") (pin "8") (pinfunction "8_8") (pintype "passive"))
      (node (ref "J11") (pin "9") (pinfunction "9_9") (pintype "passive"))
      (node (ref "J14") (pin "1") (pinfunction "1_1") (pintype "passive"))
      (node (ref "J14") (pin "2") (pinfunction "2_2") (pintype "passive"))
      (node (ref "J14") (pin "3") (pinfunction "3_3") (pintype "passive"))
      (node (ref "J14") (pin "4") (pinfunction "4_4") (pintype "passive"))
      (node (ref "J14") (pin "5") (pinfunction "5_5") (pintype "passive"))
      (node (ref "J14") (pin "6") (pinfunction "6_6") (pintype "passive"))
      (node (ref "J14") (pin "7") (pinfunction "7_7") (pintype "passive"))
      (node (ref "J14") (pin "8") (pinfunction "8_8") (pintype "passive"))
      (node (ref "J2") (pin "3") (pinfunction "3_3") (pintype "passive"))
      (node (ref "J3") (pin "3") (pinfunction "3_3") (pintype "passive"))
      (node (ref "J5") (pin "2") (pinfunction "2_2") (pintype "passive"))
      (node (ref "J6") (pin "4") (pinfunction "4_4") (pintype "passive"))
      (node (ref "J7") (pin "3") (pinfunction "3_3") (pintype "passive"))
      (node (ref "J8") (pin "1") (pinfunction "1_1") (pintype "passive"))
      (node (ref "J8") (pin "2") (pinfunction "2_2") (pintype "passive"))
      (node (ref "J8") (pin "3") (pinfunction "3_3") (pintype "passive"))
      (node (ref "J8") (pin "4") (pinfunction "4_4") (pintype "passive"))
      (node (ref "J8") (pin "5") (pinfunction "5_5") (pintype "passive"))
      (node (ref "J8") (pin "6") (pinfunction "6_6") (pintype "passive"))
      (node (ref "J8") (pin "7") (pinfunction "7_7") (pintype "passive"))
      (node (ref "J8") (pin "8") (pinfunction "8_8") (pintype "passive"))
      (node (ref "JP1") (pin "3") (pinfunction "3_3") (pintype "passive"))
      (node (ref "JP3") (pin "7") (pinfunction "7_7") (pintype "passive"))
      (node (ref "LCD") (pin "K") (pinfunction "K_K") (pintype "bidirectional"))
      (node (ref "LCD") (pin "R/W") (pinfunction "R/W_R/W") (pintype "bidirectional"))
      (node (ref "LCD") (pin "VSS") (pinfunction "VSS_VSS") (pintype "bidirectional"))
      (node (ref "LED2") (pin "C") (pinfunction "C_C") (pintype "passive"))
      (node (ref "LED3") (pin "C") (pinfunction "C_C") (pintype "passive"))
      (node (ref "LED4") (pin "C") (pinfunction "C_C") (pintype "passive"))
      (node (ref "POT") (pin "3") (pinfunction "E_3") (pintype "passive"))
      (node (ref "POWER") (pin "R") (pinfunction "R_R") (pintype "bidirectional"))
      (node (ref "Q2") (pin "2") (pinfunction "E_2") (pintype "passive"))
      (node (ref "R11") (pin "1") (pinfunction "1_1") (pintype "passive"))
      (node (ref "R19") (pin "2") (pinfunction "2_2") (pintype "passive"))
      (node (ref "R2") (pin "2") (pinfunction "2_2") (pintype "passive"))
      (node (ref "R26") (pin "1") (pinfunction "1_1") (pintype "passive"))
      (node (ref "R28") (pin "2") (pinfunction "2_2") (pintype "passive"))
      (node (ref "R33") (pin "1") (pinfunction "1_1") (pintype "passive"))
      (node (ref "R35") (pin "1") (pinfunction "1_1") (pintype "passive"))
      (node (ref "R41") (pin "2") (pinfunction "2_2") (pintype "passive"))
      (node (ref "R42") (pin "1") (pinfunction "1_1") (pintype "passive"))
      (node (ref "R43") (pin "1") (pinfunction "1_1") (pintype "passive"))
      (node (ref "R44") (pin "1") (pinfunction "1_1") (pintype "passive"))
      (node (ref "RESET") (pin "3") (pinfunction "P_3") (pintype "passive"))
      (node (ref "RESET") (pin "4") (pinfunction "P1_4") (pintype "passive"))
      (node (ref "SD") (pin "6") (pinfunction "GND_6") (pintype "bidirectional"))
      (node (ref "SD") (pin "CD1") (pinfunction "SHIELD_CD1") (pintype "bidirectional"))
      (node (ref "SD") (pin "CD2") (pinfunction "SHIELD_CD2") (pintype "bidirectional"))
      (node (ref "SD") (pin "GND1") (pinfunction "SHIELD_GND1") (pintype "bidirectional"))
      (node (ref "SD") (pin "GND3") (pinfunction "SHIELD_GND3") (pintype "bidirectional"))
      (node (ref "SERVO_PWR") (pin "R") (pinfunction "R_R") (pintype "bidirectional"))
      (node (ref "SW1") (pin "P$2") (pinfunction "P$2_P$2") (pintype "bidirectional"))
      (node (ref "U$1") (pin "1") (pinfunction "GND_1") (pintype "bidirectional"))
      (node (ref "U$1") (pin "2") (pinfunction "GND_2") (pintype "bidirectional"))
      (node (ref "U$1") (pin "26") (pinfunction "SA0_26") (pintype "bidirectional"))
      (node (ref "U$1") (pin "27") (pinfunction "SA0_27") (pintype "bidirectional"))
      (node (ref "U$1") (pin "3") (pinfunction "GND_3") (pintype "bidirectional"))
      (node (ref "U$1") (pin "4") (pinfunction "GND_4") (pintype "bidirectional"))
      (node (ref "U$1") (pin "5") (pinfunction "GND_5") (pintype "bidirectional"))
      (node (ref "U$1") (pin "6") (pinfunction "GND_6") (pintype "bidirectional"))
      (node (ref "U$12") (pin "1") (pinfunction "S_1") (pintype "bidirectional"))
      (node (ref "U$12") (pin "2") (pinfunction "S_2") (pintype "bidirectional"))
      (node (ref "U$12") (pin "3") (pinfunction "S_3") (pintype "bidirectional"))
      (node (ref "U$2") (pin "1") (pinfunction "GND_1") (pintype "bidirectional"))
      (node (ref "U$3") (pin "7") (pinfunction "GND_7") (pintype "bidirectional"))
      (node (ref "U$4") (pin "1") (pinfunction "GND_1") (pintype "bidirectional"))
      (node (ref "U$4") (pin "12") (pinfunction "GND_12") (pintype "bidirectional"))
      (node (ref "U$4") (pin "14") (pinfunction "GND_14") (pintype "bidirectional"))
      (node (ref "U$4") (pin "15") (pinfunction "SENSE_B_15") (pintype "bidirectional"))
      (node (ref "U$4") (pin "16") (pinfunction "SENSE_B_16") (pintype "bidirectional"))
      (node (ref "U$4") (pin "19") (pinfunction "PROGCLB_19") (pintype "bidirectional"))
      (node (ref "U$4") (pin "24") (pinfunction "GND_24") (pintype "bidirectional"))
      (node (ref "U$4") (pin "25") (pinfunction "GND_25") (pintype "bidirectional"))
      (node (ref "U$4") (pin "28") (pinfunction "GND_28") (pintype "bidirectional"))
      (node (ref "U$4") (pin "29") (pinfunction "GND_29") (pintype "bidirectional"))
      (node (ref "U$4") (pin "30") (pinfunction "GND_30") (pintype "bidirectional"))
      (node (ref "U$4") (pin "31") (pinfunction "GND_31") (pintype "bidirectional"))
      (node (ref "U$4") (pin "32") (pinfunction "GND_32") (pintype "bidirectional"))
      (node (ref "U$4") (pin "33") (pinfunction "GND_33") (pintype "bidirectional"))
      (node (ref "U$4") (pin "36") (pinfunction "GND_36") (pintype "bidirectional"))
      (node (ref "U$4") (pin "37") (pinfunction "GND_37") (pintype "bidirectional"))
      (node (ref "U$4") (pin "4") (pinfunction "GND_4") (pintype "bidirectional"))
      (node (ref "U$4") (pin "42") (pinfunction "PROGCLA_42") (pintype "bidirectional"))
      (node (ref "U$4") (pin "45") (pinfunction "SENSE_A_45") (pintype "bidirectional"))
      (node (ref "U$4") (pin "46") (pinfunction "SENSE_A_46") (pintype "bidirectional"))
      (node (ref "U$4") (pin "47") (pinfunction "GND_47") (pintype "bidirectional"))
      (node (ref "U$4") (pin "5") (pinfunction "GND_5") (pintype "bidirectional"))
      (node (ref "U$4") (pin "6") (pinfunction "GND_6") (pintype "bidirectional"))
      (node (ref "U$4") (pin "7") (pinfunction "GND_7") (pintype "bidirectional"))
      (node (ref "U$4") (pin "8") (pinfunction "GND_8") (pintype "bidirectional"))
      (node (ref "U$4") (pin "9") (pinfunction "GND_9") (pintype "bidirectional"))
      (node (ref "U$4") (pin "PAD") (pinfunction "GND_PAD") (pintype "bidirectional"))
      (node (ref "U$5") (pin "1") (pinfunction "GND_1") (pintype "bidirectional"))
      (node (ref "U$5") (pin "12") (pinfunction "GND_12") (pintype "bidirectional"))
      (node (ref "U$5") (pin "14") (pinfunction "GND_14") (pintype "bidirectional"))
      (node (ref "U$5") (pin "15") (pinfunction "SENSE_B_15") (pintype "bidirectional"))
      (node (ref "U$5") (pin "16") (pinfunction "SENSE_B_16") (pintype "bidirectional"))
      (node (ref "U$5") (pin "19") (pinfunction "PROGCLB_19") (pintype "bidirectional"))
      (node (ref "U$5") (pin "24") (pinfunction "GND_24") (pintype "bidirectional"))
      (node (ref "U$5") (pin "25") (pinfunction "GND_25") (pintype "bidirectional"))
      (node (ref "U$5") (pin "28") (pinfunction "GND_28") (pintype "bidirectional"))
      (node (ref "U$5") (pin "29") (pinfunction "GND_29") (pintype "bidirectional"))
      (node (ref "U$5") (pin "30") (pinfunction "GND_30") (pintype "bidirectional"))
      (node (ref "U$5") (pin "31") (pinfunction "GND_31") (pintype "bidirectional"))
      (node (ref "U$5") (pin "32") (pinfunction "GND_32") (pintype "bidirectional"))
      (node (ref "U$5") (pin "33") (pinfunction "GND_33") (pintype "bidirectional"))
      (node (ref "U$5") (pin "36") (pinfunction "GND_36") (pintype "bidirectional"))
      (node (ref "U$5") (pin "37") (pinfunction "GND_37") (pintype "bidirectional"))
      (node (ref "U$5") (pin "4") (pinfunction "GND_4") (pintype "bidirectional"))
      (node (ref "U$5") (pin "42") (pinfunction "PROGCLA_42") (pintype "bidirectional"))
      (node (ref "U$5") (pin "45") (pinfunction "SENSE_A_45") (pintype "bidirectional"))
      (node (ref "U$5") (pin "46") (pinfunction "SENSE_A_46") (pintype "bidirectional"))
      (node (ref "U$5") (pin "47") (pinfunction "GND_47") (pintype "bidirectional"))
      (node (ref "U$5") (pin "5") (pinfunction "GND_5") (pintype "bidirectional"))
      (node (ref "U$5") (pin "6") (pinfunction "GND_6") (pintype "bidirectional"))
      (node (ref "U$5") (pin "7") (pinfunction "GND_7") (pintype "bidirectional"))
      (node (ref "U$5") (pin "8") (pinfunction "GND_8") (pintype "bidirectional"))
      (node (ref "U$5") (pin "9") (pinfunction "GND_9") (pintype "bidirectional"))
      (node (ref "U$5") (pin "PAD") (pinfunction "GND_PAD") (pintype "bidirectional"))
      (node (ref "U2") (pin "14") (pinfunction "GND_14") (pintype "bidirectional"))
      (node (ref "U2") (pin "P$1") (pinfunction "GND_P$1") (pintype "bidirectional"))
      (node (ref "U3") (pin "3") (pinfunction "GND_3") (pintype "bidirectional"))
      (node (ref "U6") (pin "P$2") (pinfunction "GND_P$2") (pintype "bidirectional"))
      (node (ref "U8") (pin "P$2") (pinfunction "GND_P$2") (pintype "bidirectional"))
      (node (ref "USB1") (pin "GND") (pinfunction "GND_GND") (pintype "bidirectional"))
      (node (ref "USB1") (pin "GND@1") (pinfunction "GND_GND@1") (pintype "bidirectional"))
      (node (ref "USB1") (pin "GND@2") (pinfunction "GND_GND@2") (pintype "bidirectional"))
      (node (ref "USB2") (pin "GND") (pinfunction "GND_GND") (pintype "bidirectional"))
      (node (ref "USB2") (pin "MTN1") (pinfunction "MTN2_MTN1") (pintype "bidirectional"))
      (node (ref "USB2") (pin "MTN2") (pinfunction "MTN3_MTN2") (pintype "bidirectional"))
      (node (ref "USB2") (pin "MTN3") (pinfunction "MTN1_MTN3") (pintype "bidirectional"))
      (node (ref "USB2") (pin "MTN4") (pinfunction "MTN4_MTN4") (pintype "bidirectional"))
      (node (ref "XB1") (pin "10") (pinfunction "GND_10") (pintype "power_in"))
    )
    (net (code "92") (name "Net-(C21-Pad1)") (class "Default")
      (node (ref "C21") (pin "1") (pinfunction "1_1") (pintype "passive"))
      (node (ref "C23") (pin "1") (pinfunction "1_1") (pintype "passive"))
      (node (ref "U$2") (pin "6") (pinfunction "VOUT_6") (pintype "bidirectional"))
      (node (ref "U$2") (pin "7") (pinfunction "VOUT_7") (pintype "bidirectional"))
      (node (ref "U$2") (pin "8") (pinfunction "VOUT_8") (pintype "bidirectional"))
      (node (ref "USB1") (pin "VBUS") (pinfunction "VBUS_VBUS") (pintype "bidirectional"))
    )
    (net (code "93") (name "Net-(C29-Pad1)") (class "Default")
      (node (ref "C29") (pin "1") (pinfunction "1_1") (pintype "passive"))
      (node (ref "R3") (pin "2") (pinfunction "2_2") (pintype "passive"))
      (node (ref "U$6") (pin "1") (pinfunction "S_1") (pintype "bidirectional"))
      (node (ref "U$6") (pin "2") (pinfunction "S_2") (pintype "bidirectional"))
      (node (ref "U$6") (pin "3") (pinfunction "S_3") (pintype "bidirectional"))
      (node (ref "U$7") (pin "1") (pinfunction "S_1") (pintype "bidirectional"))
      (node (ref "U$7") (pin "2") (pinfunction "S_2") (pintype "bidirectional"))
      (node (ref "U$7") (pin "3") (pinfunction "S_3") (pintype "bidirectional"))
    )
    (net (code "94") (name "Net-(C45-Pad1)") (class "Default")
      (node (ref "C45") (pin "1") (pinfunction "1_1") (pintype "passive"))
      (node (ref "R12") (pin "1") (pinfunction "1_1") (pintype "passive"))
    )
    (net (code "95") (name "Net-(C49-Pad1)") (class "Default")
      (node (ref "C49") (pin "1") (pinfunction "1_1") (pintype "passive"))
      (node (ref "R13") (pin "1") (pinfunction "1_1") (pintype "passive"))
    )
    (net (code "96") (name "Net-(F1-Pad1)") (class "Default")
      (node (ref "F1") (pin "1") (pinfunction "1_1") (pintype "bidirectional"))
      (node (ref "Q1") (pin "4") (pinfunction "S_4") (pintype "bidirectional"))
      (node (ref "Q1") (pin "7") (pinfunction "S_7") (pintype "bidirectional"))
    )
    (net (code "97") (name "Net-(IC3A-VCAP_2)") (class "Default")
      (node (ref "C37") (pin "1") (pinfunction "1_1") (pintype "passive"))
      (node (ref "IC3") (pin "73") (pinfunction "VCAP_2_73") (pintype "power_in"))
    )
    (net (code "98") (name "Net-(IC3B-OSC_IN)") (class "Default")
      (node (ref "C19") (pin "1") (pinfunction "1_1") (pintype "passive"))
      (node (ref "IC3") (pin "12") (pinfunction "OSC_IN_12") (pintype "input"))
      (node (ref "Y2") (pin "2") (pinfunction "2_2") (pintype "passive"))
    )
    (net (code "99") (name "Net-(IC3B-OSC_OUT)") (class "Default")
      (node (ref "C2") (pin "1") (pinfunction "1_1") (pintype "passive"))
      (node (ref "IC3") (pin "13") (pinfunction "OSC_OUT_13") (pintype "output"))
      (node (ref "Y2") (pin "1") (pinfunction "1_1") (pintype "passive"))
    )
    (net (code "100") (name "Net-(IC3M-VCAP_1)") (class "Default")
      (node (ref "C7") (pin "1") (pinfunction "1_1") (pintype "passive"))
      (node (ref "IC3") (pin "49") (pinfunction "VCAP_1_49") (pintype "power_in"))
    )
    (net (code "101") (name "Net-(IC3N-BOOT0)") (class "Default")
      (node (ref "IC3") (pin "94") (pinfunction "BOOT0_94") (pintype "input"))
      (node (ref "R42") (pin "2") (pinfunction "2_2") (pintype "passive"))
    )
    (net (code "102") (name "Net-(IC4A-+IN)") (class "Default")
      (node (ref "IC4") (pin "3") (pinfunction "+IN_3") (pintype "input"))
      (node (ref "R10") (pin "1") (pinfunction "1_1") (pintype "passive"))
      (node (ref "R11") (pin "2") (pinfunction "2_2") (pintype "passive"))
    )
    (net (code "103") (name "Net-(IC4A-OUT)") (class "Default")
      (node (ref "IC4") (pin "1") (pinfunction "OUT_1") (pintype "output"))
      (node (ref "Q1") (pin "3") (pinfunction "G_3") (pintype "bidirectional"))
    )
    (net (code "104") (name "Net-(IC4B-+IN)") (class "Default")
      (node (ref "IC4") (pin "5") (pinfunction "+IN_5") (pintype "input"))
      (node (ref "R28") (pin "1") (pinfunction "1_1") (pintype "passive"))
      (node (ref "R29") (pin "2") (pinfunction "2_2") (pintype "passive"))
    )
    (net (code "105") (name "Net-(IC4B--IN)") (class "Default")
      (node (ref "IC4") (pin "6") (pinfunction "-IN_6") (pintype "input"))
      (node (ref "R26") (pin "2") (pinfunction "2_2") (pintype "passive"))
      (node (ref "R27") (pin "1") (pinfunction "1_1") (pintype "passive"))
    )
    (net (code "106") (name "Net-(IC4B-OUT)") (class "Default")
      (node (ref "IC4") (pin "7") (pinfunction "OUT_7") (pintype "output"))
      (node (ref "R36") (pin "1") (pinfunction "1_1") (pintype "passive"))
      (node (ref "U3") (pin "2") (pinfunction "A_2") (pintype "bidirectional"))
    )
    (net (code "107") (name "Net-(J12-Pad1)") (class "Default")
      (node (ref "J12") (pin "1") (pinfunction "1_1") (pintype "passive"))
      (node (ref "J12") (pin "10") (pinfunction "10_10") (pintype "passive"))
      (node (ref "J12") (pin "11") (pinfunction "11_11") (pintype "passive"))
      (node (ref "J12") (pin "12") (pinfunction "12_12") (pintype "passive"))
      (node (ref "J12") (pin "13") (pinfunction "13_13") (pintype "passive"))
      (node (ref "J12") (pin "14") (pinfunction "14_14") (pintype "passive"))
      (node (ref "J12") (pin "15") (pinfunction "15_15") (pintype "passive"))
      (node (ref "J12") (pin "2") (pinfunction "2_2") (pintype "passive"))
      (node (ref "J12") (pin "3") (pinfunction "3_3") (pintype "passive"))
      (node (ref "J12") (pin "4") (pinfunction "4_4") (pintype "passive"))
      (node (ref "J12") (pin "5") (pinfunction "5_5") (pintype "passive"))
      (node (ref "J12") (pin "6") (pinfunction "6_6") (pintype "passive"))
      (node (ref "J12") (pin "7") (pinfunction "7_7") (pintype "passive"))
      (node (ref "J12") (pin "8") (pinfunction "8_8") (pintype "passive"))
      (node (ref "J12") (pin "9") (pinfunction "9_9") (pintype "passive"))
      (node (ref "JP2") (pin "2") (pinfunction "2_2") (pintype "passive"))
    )
    (net (code "108") (name "Net-(L1-1)") (class "Default")
      (node (ref "C32") (pin "2") (pinfunction "2_2") (pintype "passive"))
      (node (ref "L1") (pin "P$1") (pinfunction "1_P$1") (pintype "passive"))
      (node (ref "U$12") (pin "5") (pinfunction "D_5") (pintype "bidirectional"))
      (node (ref "U2") (pin "10") (pinfunction "SW_10") (pintype "bidirectional"))
      (node (ref "U2") (pin "8") (pinfunction "SW_8") (pintype "bidirectional"))
      (node (ref "U2") (pin "9") (pinfunction "SW_9") (pintype "bidirectional"))
    )
    (net (code "109") (name "Net-(LCD-PadA)") (class "Default")
      (node (ref "LCD") (pin "A") (pinfunction "A_A") (pintype "bidirectional"))
      (node (ref "R1") (pin "1") (pinfunction "1_1") (pintype "passive"))
    )
    (net (code "110") (name "Net-(LD1085-ADJ)") (class "Default")
      (node (ref "C38") (pin "2") (pinfunction "2_2") (pintype "passive"))
      (node (ref "LD1085") (pin "1") (pinfunction "ADJ_1") (pintype "bidirectional"))
      (node (ref "R44") (pin "2") (pinfunction "2_2") (pintype "passive"))
      (node (ref "R45") (pin "1") (pinfunction "1_1") (pintype "passive"))
    )
    (net (code "111") (name "Net-(LED2-PadA)") (class "Default")
      (node (ref "LED2") (pin "A") (pinfunction "A_A") (pintype "passive"))
      (node (ref "R20") (pin "1") (pinfunction "1_1") (pintype "passive"))
    )
    (net (code "112") (name "Net-(LED3-PadA)") (class "Default")
      (node (ref "LED3") (pin "A") (pinfunction "A_A") (pintype "passive"))
      (node (ref "R21") (pin "1") (pinfunction "1_1") (pintype "passive"))
    )
    (net (code "113") (name "Net-(LED4-PadA)") (class "Default")
      (node (ref "LED4") (pin "A") (pinfunction "A_A") (pintype "passive"))
      (node (ref "R4") (pin "1") (pinfunction "1_1") (pintype "passive"))
    )
    (net (code "114") (name "Net-(LED5-PadC)") (class "Default")
      (node (ref "LED5") (pin "C") (pinfunction "C_C") (pintype "passive"))
      (node (ref "R35") (pin "2") (pinfunction "2_2") (pintype "passive"))
    )
    (net (code "115") (name "Net-(LED6-Pad1)") (class "Default")
      (node (ref "LED6") (pin "1") (pinfunction "1_1") (pintype "passive"))
      (node (ref "LED6") (pin "4") (pinfunction "4_4") (pintype "passive"))
      (node (ref "R37") (pin "2") (pinfunction "2_2") (pintype "passive"))
    )
    (net (code "116") (name "Net-(LED7-Pad1)") (class "Default")
      (node (ref "LED7") (pin "1") (pinfunction "1_1") (pintype "passive"))
      (node (ref "LED7") (pin "4") (pinfunction "4_4") (pintype "passive"))
      (node (ref "R38") (pin "2") (pinfunction "2_2") (pintype "passive"))
    )
    (net (code "117") (name "Net-(POT-S)") (class "Default")
      (node (ref "LCD") (pin "VO") (pinfunction "VO_VO") (pintype "bidirectional"))
      (node (ref "POT") (pin "2") (pinfunction "S_2") (pintype "passive"))
    )
    (net (code "118") (name "Net-(POWER-PadL)") (class "Default")
      (node (ref "POWER") (pin "L") (pinfunction "L_L") (pintype "bidirectional"))
      (node (ref "U$6") (pin "5") (pinfunction "D_5") (pintype "bidirectional"))
      (node (ref "U$6") (pin "6") (pinfunction "D_6") (pintype "bidirectional"))
      (node (ref "U$6") (pin "7") (pinfunction "D_7") (pintype "bidirectional"))
      (node (ref "U$6") (pin "8") (pinfunction "D_8") (pintype "bidirectional"))
      (node (ref "U$6") (pin "PAD") (pinfunction "D_PAD") (pintype "bidirectional"))
    )
    (net (code "119") (name "Net-(Q2-B)") (class "Default")
      (node (ref "Q2") (pin "1") (pinfunction "B_1") (pintype "passive"))
      (node (ref "R39") (pin "2") (pinfunction "2_2") (pintype "passive"))
    )
    (net (code "120") (name "Net-(Q2-C)") (class "Default")
      (node (ref "Q2") (pin "3") (pinfunction "C_3") (pintype "passive"))
      (node (ref "SG1") (pin "-") (pinfunction "2_-") (pintype "passive"))
    )
    (net (code "121") (name "Net-(R12-Pad2)") (class "Default")
      (node (ref "R12") (pin "2") (pinfunction "2_2") (pintype "passive"))
      (node (ref "U$10") (pin "2") (pinfunction "2_2") (pintype "bidirectional"))
    )
    (net (code "122") (name "Net-(R13-Pad2)") (class "Default")
      (node (ref "R13") (pin "2") (pinfunction "2_2") (pintype "passive"))
      (node (ref "U$11") (pin "2") (pinfunction "2_2") (pintype "bidirectional"))
    )
    (net (code "123") (name "Net-(R31-Pad2)") (class "Default")
      (node (ref "R31") (pin "2") (pinfunction "2_2") (pintype "passive"))
      (node (ref "SW1") (pin "P$1") (pinfunction "P$1_P$1") (pintype "bidirectional"))
    )
    (net (code "124") (name "Net-(U$1-CAP)") (class "Default")
      (node (ref "C35") (pin "1") (pinfunction "1_1") (pintype "passive"))
      (node (ref "U$1") (pin "15") (pinfunction "CAP_15") (pintype "bidirectional"))
    )
    (net (code "125") (name "Net-(U$3-QA)") (class "Default")
      (node (ref "LCD") (pin "DB0") (pinfunction "DB0_DB0") (pintype "bidirectional"))
      (node (ref "U$3") (pin "3") (pinfunction "QA_3") (pintype "bidirectional"))
    )
    (net (code "126") (name "Net-(U$3-QB)") (class "Default")
      (node (ref "LCD") (pin "DB1") (pinfunction "DB1_DB1") (pintype "bidirectional"))
      (node (ref "U$3") (pin "4") (pinfunction "QB_4") (pintype "bidirectional"))
    )
    (net (code "127") (name "Net-(U$3-QC)") (class "Default")
      (node (ref "LCD") (pin "DB2") (pinfunction "DB2_DB2") (pintype "bidirectional"))
      (node (ref "U$3") (pin "5") (pinfunction "QC_5") (pintype "bidirectional"))
    )
    (net (code "128") (name "Net-(U$3-QD)") (class "Default")
      (node (ref "LCD") (pin "DB3") (pinfunction "DB3_DB3") (pintype "bidirectional"))
      (node (ref "U$3") (pin "6") (pinfunction "QD_6") (pintype "bidirectional"))
    )
    (net (code "129") (name "Net-(U$3-QE)") (class "Default")
      (node (ref "LCD") (pin "DB4") (pinfunction "DB4_DB4") (pintype "bidirectional"))
      (node (ref "U$3") (pin "10") (pinfunction "QE_10") (pintype "bidirectional"))
    )
    (net (code "130") (name "Net-(U$3-QF)") (class "Default")
      (node (ref "LCD") (pin "DB5") (pinfunction "DB5_DB5") (pintype "bidirectional"))
      (node (ref "U$3") (pin "11") (pinfunction "QF_11") (pintype "bidirectional"))
    )
    (net (code "131") (name "Net-(U$3-QG)") (class "Default")
      (node (ref "LCD") (pin "DB6") (pinfunction "DB6_DB6") (pintype "bidirectional"))
      (node (ref "U$3") (pin "12") (pinfunction "QG_12") (pintype "bidirectional"))
    )
    (net (code "132") (name "Net-(U$3-QH)") (class "Default")
      (node (ref "LCD") (pin "DB7") (pinfunction "DB7_DB7") (pintype "bidirectional"))
      (node (ref "U$3") (pin "13") (pinfunction "QH_13") (pintype "bidirectional"))
    )
    (net (code "133") (name "Net-(U$4-VBOOT)") (class "Default")
      (node (ref "C48") (pin "2") (pinfunction "2_2") (pintype "passive"))
      (node (ref "U$11") (pin "3") (pinfunction "3_3") (pintype "bidirectional"))
      (node (ref "U$4") (pin "21") (pinfunction "VBOOT_21") (pintype "bidirectional"))
    )
    (net (code "134") (name "Net-(U$4-VCP)") (class "Default")
      (node (ref "C49") (pin "2") (pinfunction "2_2") (pintype "passive"))
      (node (ref "U$4") (pin "40") (pinfunction "VCP_40") (pintype "bidirectional"))
    )
    (net (code "135") (name "Net-(U$5-VBOOT)") (class "Default")
      (node (ref "C20") (pin "2") (pinfunction "2_2") (pintype "passive"))
      (node (ref "U$10") (pin "3") (pinfunction "3_3") (pintype "bidirectional"))
      (node (ref "U$5") (pin "21") (pinfunction "VBOOT_21") (pintype "bidirectional"))
    )
    (net (code "136") (name "Net-(U$5-VCP)") (class "Default")
      (node (ref "C45") (pin "2") (pinfunction "2_2") (pintype "passive"))
      (node (ref "U$5") (pin "40") (pinfunction "VCP_40") (pintype "bidirectional"))
    )
    (net (code "137") (name "Net-(U$6-G)") (class "Default")
      (node (ref "C29") (pin "2") (pinfunction "2_2") (pintype "passive"))
      (node (ref "R2") (pin "1") (pinfunction "1_1") (pintype "passive"))
      (node (ref "U$6") (pin "4") (pinfunction "G_4") (pintype "bidirectional"))
    )
    (net (code "138") (name "Net-(U$7-G)") (class "Default")
      (node (ref "R3") (pin "1") (pinfunction "1_1") (pintype "passive"))
      (node (ref "R31") (pin "1") (pinfunction "1_1") (pintype "passive"))
      (node (ref "U$7") (pin "4") (pinfunction "G_4") (pintype "bidirectional"))
    )
    (net (code "139") (name "Net-(U$8-G)") (class "Default")
      (node (ref "U$8") (pin "4") (pinfunction "G_4") (pintype "bidirectional"))
      (node (ref "U3") (pin "4") (pinfunction "Y_4") (pintype "bidirectional"))
    )
    (net (code "140") (name "Net-(U$12-G)") (class "Default")
      (node (ref "U$12") (pin "4") (pinfunction "G_4") (pintype "bidirectional"))
      (node (ref "U2") (pin "13") (pinfunction "BG_13") (pintype "bidirectional"))
    )
    (net (code "141") (name "Net-(U2-BOOT)") (class "Default")
      (node (ref "C32") (pin "1") (pinfunction "1_1") (pintype "passive"))
      (node (ref "U2") (pin "11") (pinfunction "BOOT_11") (pintype "bidirectional"))
    )
    (net (code "142") (name "Net-(U2-EN{slash}SYNC)") (class "Default")
      (node (ref "R34") (pin "1") (pinfunction "1_1") (pintype "passive"))
      (node (ref "U2") (pin "3") (pinfunction "EN/SYNC_3") (pintype "bidirectional"))
    )
    (net (code "143") (name "Net-(U2-FB)") (class "Default")
      (node (ref "R32") (pin "1") (pinfunction "1_1") (pintype "passive"))
      (node (ref "R33") (pin "2") (pinfunction "2_2") (pintype "passive"))
      (node (ref "U2") (pin "1") (pinfunction "FB_1") (pintype "bidirectional"))
    )
    (net (code "144") (name "Net-(U2-VCC)") (class "Default")
      (node (ref "C33") (pin "2") (pinfunction "2_2") (pintype "passive"))
      (node (ref "U2") (pin "12") (pinfunction "VCC_12") (pintype "bidirectional"))
    )
    (net (code "145") (name "Net-(U6-IO1_1)") (class "Default")
      (node (ref "U6") (pin "P$1") (pinfunction "IO1_1_P$1") (pintype "bidirectional"))
      (node (ref "USB1") (pin "D-") (pinfunction "D-_D-") (pintype "bidirectional"))
    )
    (net (code "146") (name "Net-(U6-IO1_2)") (class "Default")
      (node (ref "R49") (pin "1") (pinfunction "1_1") (pintype "passive"))
      (node (ref "U6") (pin "P$6") (pinfunction "IO1_2_P$6") (pintype "bidirectional"))
    )
    (net (code "147") (name "Net-(U6-IO2_1)") (class "Default")
      (node (ref "U6") (pin "P$3") (pinfunction "IO2_1_P$3") (pintype "bidirectional"))
      (node (ref "USB1") (pin "D+") (pinfunction "D+_D+") (pintype "bidirectional"))
    )
    (net (code "148") (name "Net-(U6-IO2_2)") (class "Default")
      (node (ref "R48") (pin "1") (pinfunction "1_1") (pintype "passive"))
      (node (ref "U6") (pin "P$4") (pinfunction "IO2_2_P$4") (pintype "bidirectional"))
    )
    (net (code "149") (name "Net-(U8-IO1_1)") (class "Default")
      (node (ref "U8") (pin "P$1") (pinfunction "IO1_1_P$1") (pintype "bidirectional"))
      (node (ref "USB2") (pin "D-") (pinfunction "D-_D-") (pintype "bidirectional"))
    )
    (net (code "150") (name "Net-(U8-IO1_2)") (class "Default")
      (node (ref "R46") (pin "1") (pinfunction "1_1") (pintype "passive"))
      (node (ref "U8") (pin "P$6") (pinfunction "IO1_2_P$6") (pintype "bidirectional"))
    )
    (net (code "151") (name "Net-(U8-IO2_1)") (class "Default")
      (node (ref "U8") (pin "P$3") (pinfunction "IO2_1_P$3") (pintype "bidirectional"))
      (node (ref "USB2") (pin "D+") (pinfunction "D+_D+") (pintype "bidirectional"))
    )
    (net (code "152") (name "Net-(U8-IO2_2)") (class "Default")
      (node (ref "R47") (pin "1") (pinfunction "1_1") (pintype "passive"))
      (node (ref "U8") (pin "P$4") (pinfunction "IO2_2_P$4") (pintype "bidirectional"))
    )
    (net (code "153") (name "Net-(XB1-PWM0{slash}RSSI)") (class "Default")
      (node (ref "LED5") (pin "A") (pinfunction "A_A") (pintype "passive"))
      (node (ref "XB1") (pin "6") (pinfunction "PWM0/RSSI_6") (pintype "output"))
    )
    (net (code "154") (name "unconnected-(J6-Pad1)") (class "Default")
      (node (ref "J6") (pin "1") (pinfunction "1_1") (pintype "passive"))
    )
    (net (code "155") (name "unconnected-(J6-Pad6)") (class "Default")
      (node (ref "J6") (pin "6") (pinfunction "6_6") (pintype "passive"))
    )
    (net (code "156") (name "unconnected-(SD-NC-Pad1)") (class "Default")
      (node (ref "SD") (pin "1") (pinfunction "NC_1") (pintype "bidirectional"))
    )
    (net (code "157") (name "unconnected-(SD-RSV-Pad8)") (class "Default")
      (node (ref "SD") (pin "8") (pinfunction "RSV_8") (pintype "bidirectional"))
    )
    (net (code "158") (name "unconnected-(U2-PGOOD-Pad2)") (class "Default")
      (node (ref "U2") (pin "2") (pinfunction "PGOOD_2") (pintype "bidirectional"))
    )
    (net (code "159") (name "unconnected-(U3-NC-Pad1)") (class "Default")
      (node (ref "U3") (pin "1") (pinfunction "NC_1") (pintype "bidirectional"))
    )
    (net (code "160") (name "unconnected-(USB2-PadID)") (class "Default")
      (node (ref "USB2") (pin "ID") (pinfunction "ID_ID") (pintype "bidirectional"))
    )
    (net (code "161") (name "unconnected-(XB1-AD0{slash}DIO0-Pad20)") (class "Default")
      (node (ref "XB1") (pin "20") (pinfunction "AD0/DIO0_20") (pintype "bidirectional"))
    )
    (net (code "162") (name "unconnected-(XB1-AD1{slash}DIO1-Pad19)") (class "Default")
      (node (ref "XB1") (pin "19") (pinfunction "AD1/DIO1_19") (pintype "bidirectional"))
    )
    (net (code "163") (name "unconnected-(XB1-AD2{slash}DIO2-Pad18)") (class "Default")
      (node (ref "XB1") (pin "18") (pinfunction "AD2/DIO2_18") (pintype "bidirectional"))
    )
    (net (code "164") (name "unconnected-(XB1-ASSOC{slash}AD5{slash}DIO5-Pad15)") (class "Default")
      (node (ref "XB1") (pin "15") (pinfunction "ASSOC/AD5/DIO5_15") (pintype "bidirectional"))
    )
    (net (code "165") (name "unconnected-(XB1-CD{slash}DOUT_EN{slash}DO8-Pad4)") (class "Default")
      (node (ref "XB1") (pin "4") (pinfunction "CD/DOUT_EN/DO8_4") (pintype "output"))
    )
    (net (code "166") (name "unconnected-(XB1-COORD_SEL{slash}AD3{slash}DIO3-Pad17)") (class "Default")
      (node (ref "XB1") (pin "17") (pinfunction "COORD_SEL/AD3/DIO3_17") (pintype "bidirectional"))
    )
    (net (code "167") (name "unconnected-(XB1-ON{slash}~{SLEEP}-Pad13)") (class "Default")
      (node (ref "XB1") (pin "13") (pinfunction "ON/~{SLEEP}_13") (pintype "output"))
    )
    (net (code "168") (name "unconnected-(XB1-RF_TX{slash}AD4{slash}DIO4-Pad11)") (class "Default")
      (node (ref "XB1") (pin "11") (pinfunction "RF_TX/AD4/DIO4_11") (pintype "bidirectional"))
    )
    (net (code "169") (name "unconnected-(XB1-VREF-Pad14)") (class "Default")
      (node (ref "XB1") (pin "14") (pinfunction "VREF_14") (pintype "input"))
    )
    (net (code "170") (name "unconnected-(XB1-~{CTS}{slash}DIO7-Pad12)") (class "Default")
      (node (ref "XB1") (pin "12") (pinfunction "~{CTS}/DIO7_12") (pintype "bidirectional"))
    )
    (net (code "171") (name "unconnected-(XB1-~{DTR}{slash}SLEEP_RQ{slash}DI8-Pad9)") (class "Default")
      (node (ref "XB1") (pin "9") (pinfunction "~{DTR}/SLEEP_RQ/DI8_9") (pintype "bidirectional"))
    )
    (net (code "172") (name "unconnected-(XB1-~{RESET}-Pad5)") (class "Default")
      (node (ref "XB1") (pin "5") (pinfunction "~{RESET}_5") (pintype "input"))
    )
    (net (code "173") (name "unconnected-(XB1-~{RTS}{slash}AD6{slash}DIO6-Pad16)") (class "Default")
      (node (ref "XB1") (pin "16") (pinfunction "~{RTS}/AD6/DIO6_16") (pintype "bidirectional"))
    )
  )
)
